# TN_Deck__Main_Board.net
KiCad netlist of a schematic drawn in EAGLE
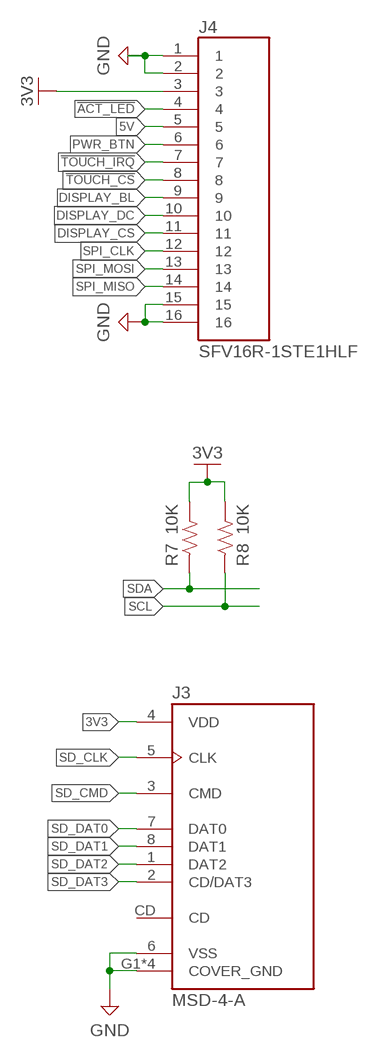
[diagram p0: schematic, sheet 1, part 1 of 2]
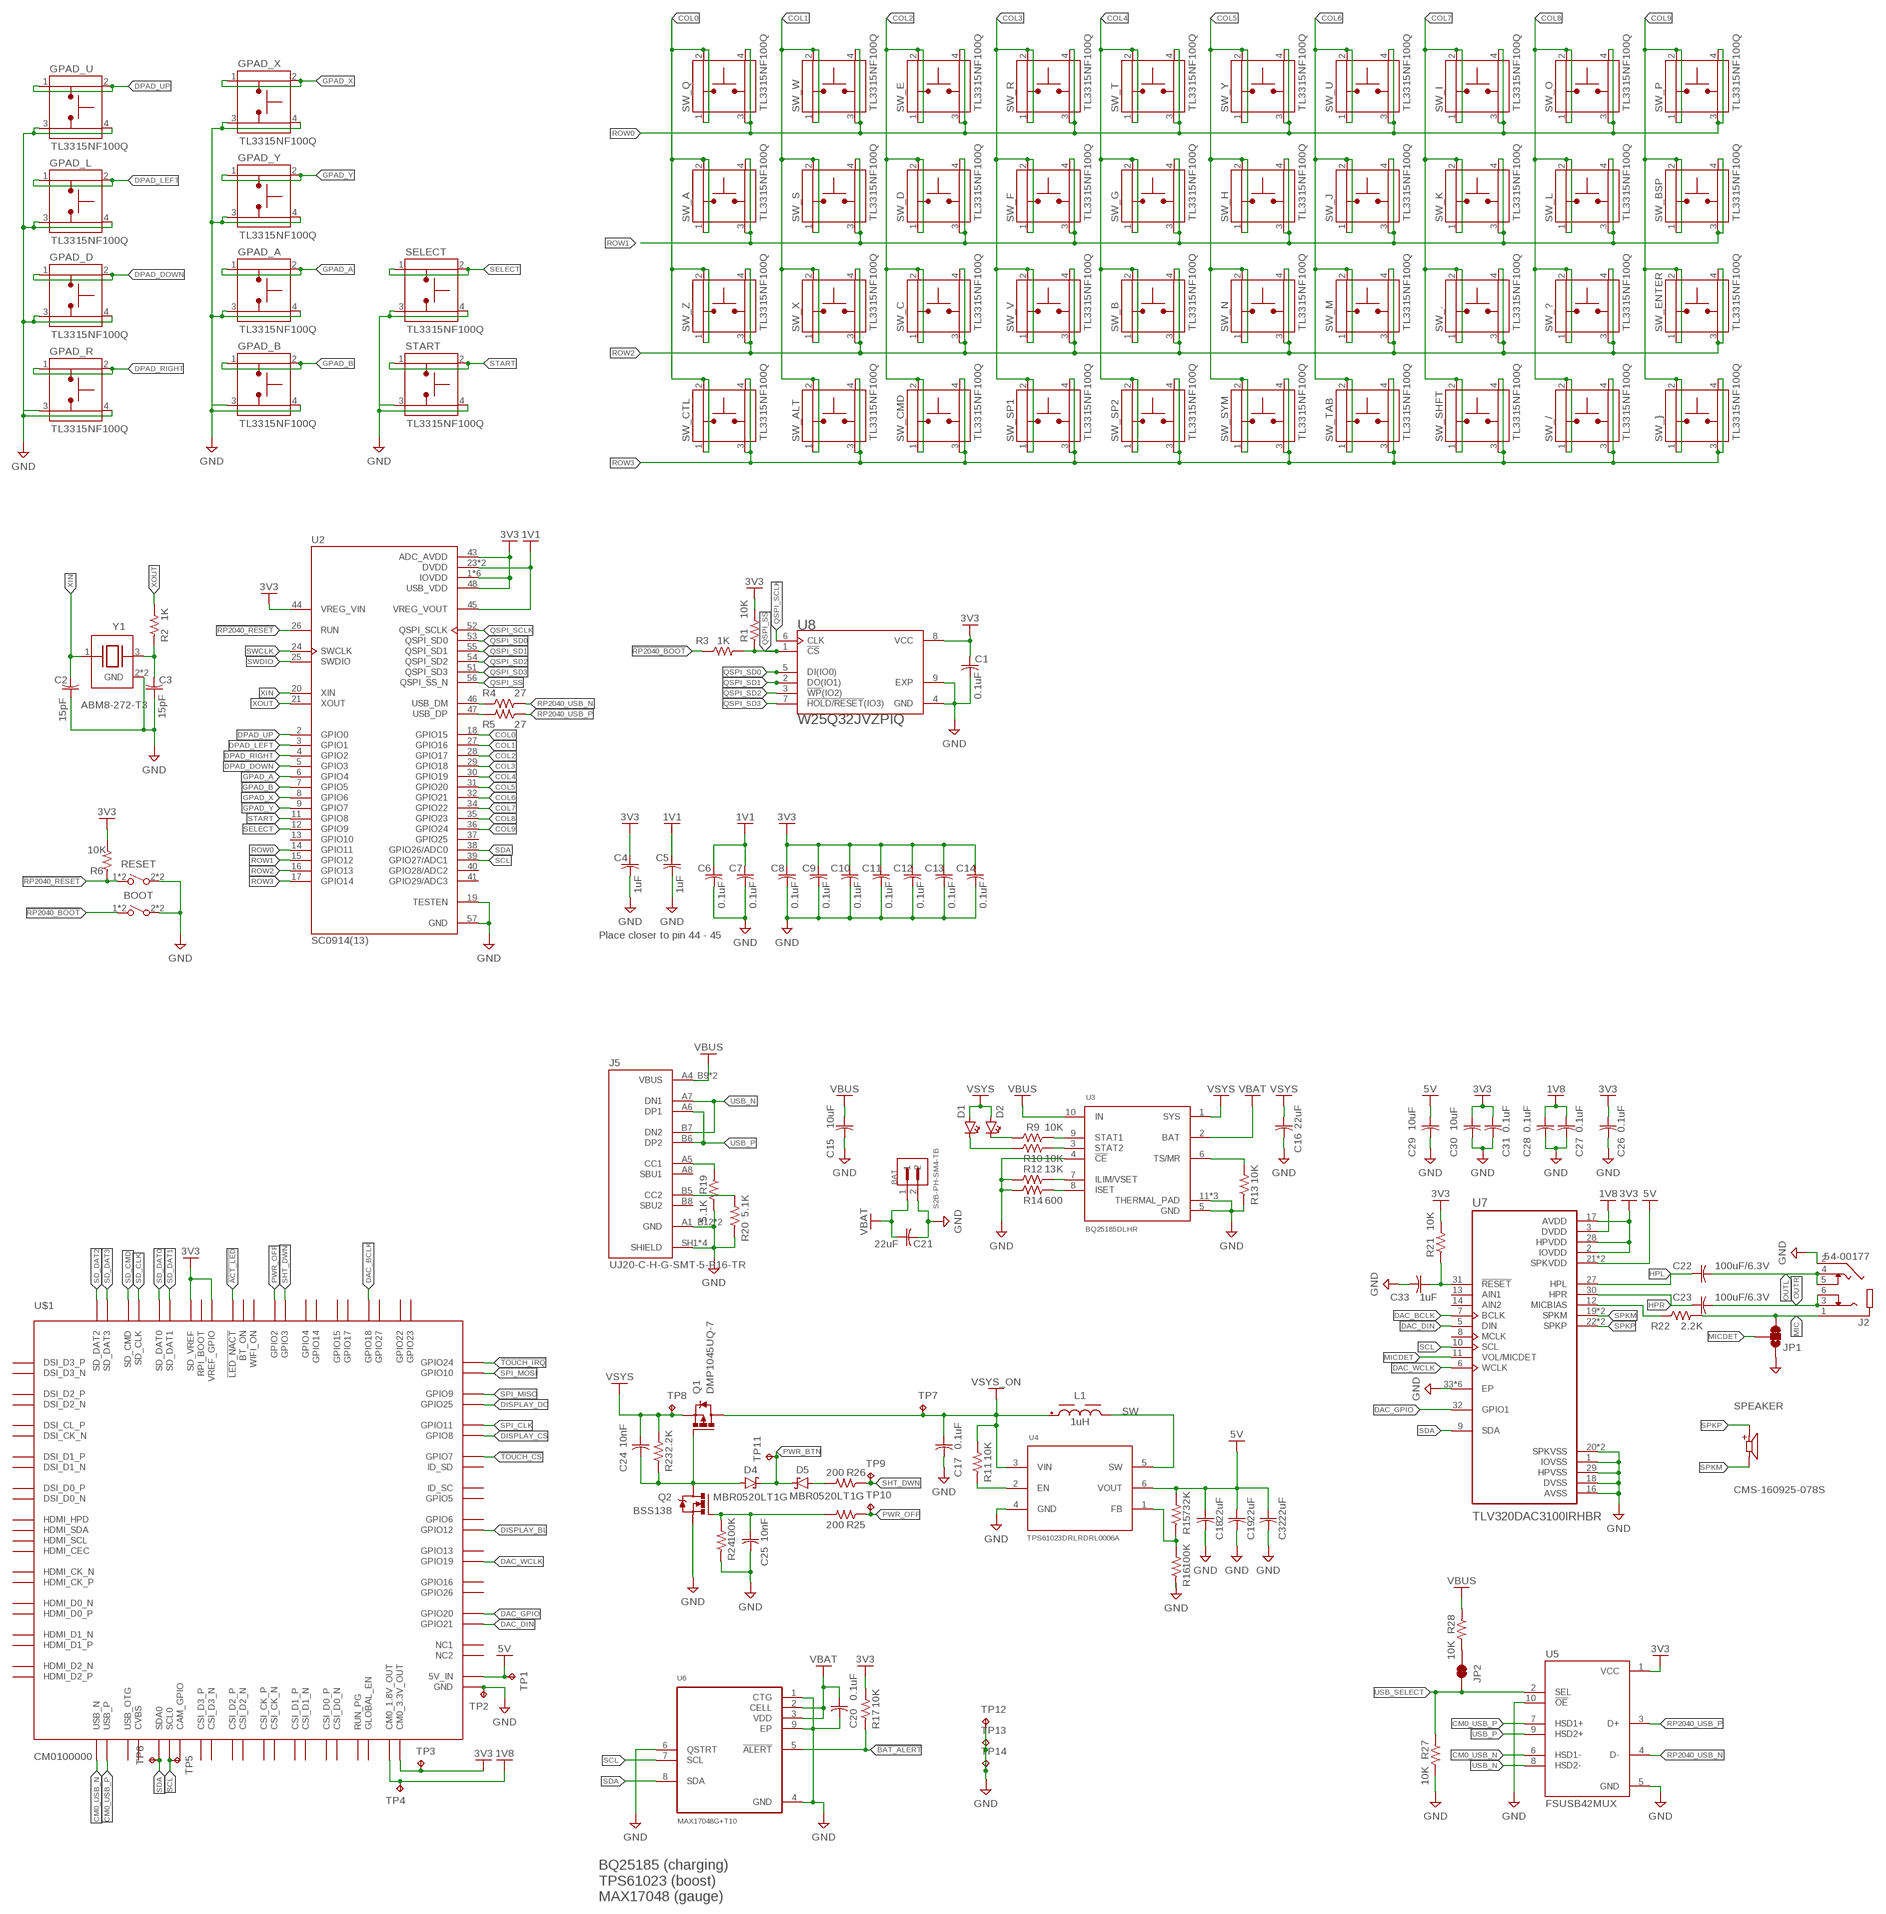
[diagram p1: schematic, sheet 1, part 2 of 2]

(export (version "E")
  (design (tool "Eeschema 10.0.6"))
  (components
    (comp (ref "BAT")
      (value "S2B-PH-SM4-TB")
      (footprint "eagle-import:JST_S2B-PH-SM4-TB")
      (fields
        (field (name "MANUFACTURER") "JST")
        (field (name "VENDOR") "Digikey")
        (field (name "VPN") "455-S2B-PH-SM4-TBCT-ND")
      )
      (libsource (lib "eagle-import") (part "S2B-PH-SM4-TB"))
    )
    (comp (ref "BOOT")
      (value "SPST-NO_SWITCH_KMR2")
      (footprint "eagle-import:KMR2")
      (fields
        (field (name "MANUFACTURER") "C&K")
        (field (name "MPN") "KMR211G LFS")
        (field (name "VENDOR") "Digikey")
        (field (name "VPN") "401-1426-1-ND")
      )
      (libsource (lib "eagle-import") (part "SPST-NO_SWITCH_KMR2"))
    )
    (comp (ref "C1")
      (value "0.1uF")
      (footprint "eagle-import:CAPC1608X85")
      (fields (field (name "VENDOR") "Digikey") (field (name "VPN") "399-C0603C104K3RACTUCT-ND"))
      (libsource (lib "eagle-import") (part "C-USCHIP-0603(1608-METRIC)_"))
    )
    (comp (ref "C2")
      (value "15pF")
      (footprint "eagle-import:CAPC1608X85")
      (fields (field (name "VENDOR") "Digikey") (field (name "VPN") "732-7761-1-ND"))
      (libsource (lib "eagle-import") (part "C-USCHIP-0603(1608-METRIC)_"))
    )
    (comp (ref "C3")
      (value "15pF")
      (footprint "eagle-import:CAPC1608X85")
      (fields (field (name "VENDOR") "Digikey") (field (name "VPN") "732-7761-1-ND"))
      (libsource (lib "eagle-import") (part "C-USCHIP-0603(1608-METRIC)_"))
    )
    (comp (ref "C4")
      (value "1uF")
      (footprint "eagle-import:CAPC1608X85")
      (fields (field (name "VENDOR") "Digikey") (field (name "VPN") "399-C0603C105K4RACTUCT-ND"))
      (libsource (lib "eagle-import") (part "C-USCHIP-0603(1608-METRIC)_"))
    )
    (comp (ref "C5")
      (value "1uF")
      (footprint "eagle-import:CAPC1608X85")
      (fields (field (name "VENDOR") "Digikey") (field (name "VPN") "399-C0603C105K4RACTUCT-ND"))
      (libsource (lib "eagle-import") (part "C-USCHIP-0603(1608-METRIC)_"))
    )
    (comp (ref "C6")
      (value "0.1uF")
      (footprint "eagle-import:CAPC1608X85")
      (fields (field (name "VENDOR") "Digikey") (field (name "VPN") "399-C0603C104K3RACTUCT-ND"))
      (libsource (lib "eagle-import") (part "C-USCHIP-0603(1608-METRIC)_"))
    )
    (comp (ref "C7")
      (value "0.1uF")
      (footprint "eagle-import:CAPC1608X85")
      (fields (field (name "VENDOR") "Digikey") (field (name "VPN") "399-C0603C104K3RACTUCT-ND"))
      (libsource (lib "eagle-import") (part "C-USCHIP-0603(1608-METRIC)_"))
    )
    (comp (ref "C8")
      (value "0.1uF")
      (footprint "eagle-import:CAPC1608X85")
      (fields (field (name "VENDOR") "Digikey") (field (name "VPN") "399-C0603C104K3RACTUCT-ND"))
      (libsource (lib "eagle-import") (part "C-USCHIP-0603(1608-METRIC)_"))
    )
    (comp (ref "C9")
      (value "0.1uF")
      (footprint "eagle-import:CAPC1608X85")
      (fields (field (name "VENDOR") "Digikey") (field (name "VPN") "399-C0603C104K3RACTUCT-ND"))
      (libsource (lib "eagle-import") (part "C-USCHIP-0603(1608-METRIC)_"))
    )
    (comp (ref "C10")
      (value "0.1uF")
      (footprint "eagle-import:CAPC1608X85")
      (fields (field (name "VENDOR") "Digikey") (field (name "VPN") "399-C0603C104K3RACTUCT-ND"))
      (libsource (lib "eagle-import") (part "C-USCHIP-0603(1608-METRIC)_"))
    )
    (comp (ref "C11")
      (value "0.1uF")
      (footprint "eagle-import:CAPC1608X85")
      (fields (field (name "VENDOR") "Digikey") (field (name "VPN") "399-C0603C104K3RACTUCT-ND"))
      (libsource (lib "eagle-import") (part "C-USCHIP-0603(1608-METRIC)_"))
    )
    (comp (ref "C12")
      (value "0.1uF")
      (footprint "eagle-import:CAPC1608X85")
      (fields (field (name "VENDOR") "Digikey") (field (name "VPN") "399-C0603C104K3RACTUCT-ND"))
      (libsource (lib "eagle-import") (part "C-USCHIP-0603(1608-METRIC)_"))
    )
    (comp (ref "C13")
      (value "0.1uF")
      (footprint "eagle-import:CAPC1608X85")
      (fields (field (name "VENDOR") "Digikey") (field (name "VPN") "399-C0603C104K3RACTUCT-ND"))
      (libsource (lib "eagle-import") (part "C-USCHIP-0603(1608-METRIC)_"))
    )
    (comp (ref "C14")
      (value "0.1uF")
      (footprint "eagle-import:CAPC1608X85")
      (fields (field (name "VENDOR") "Digikey") (field (name "VPN") "399-C0603C104K3RACTUCT-ND"))
      (libsource (lib "eagle-import") (part "C-USCHIP-0603(1608-METRIC)_"))
    )
    (comp (ref "C15")
      (value "10uF")
      (footprint "eagle-import:CAPC2012X110")
      (fields (field (name "VENDOR") "Digikey") (field (name "VPN") "1292-0805X106K250CT-ND"))
      (libsource (lib "eagle-import") (part "C-USCHIP-0805(2012-METRIC)_"))
    )
    (comp (ref "C16")
      (value "22uF")
      (footprint "eagle-import:CAPC2012X110")
      (fields (field (name "VENDOR") "Digikey") (field (name "VPN") "4713-GMC21X5R226M16NTCT-ND"))
      (libsource (lib "eagle-import") (part "C-USCHIP-0805(2012-METRIC)_"))
    )
    (comp (ref "C17")
      (value "0.1uF")
      (footprint "eagle-import:CAPC1608X85")
      (fields (field (name "VENDOR") "Digikey") (field (name "VPN") "399-C0603C104K3RACTUCT-ND"))
      (libsource (lib "eagle-import") (part "C-USCHIP-0603(1608-METRIC)_"))
    )
    (comp (ref "C18")
      (value "22uF")
      (footprint "eagle-import:CAPC2012X110")
      (fields (field (name "VENDOR") "Digikey") (field (name "VPN") "4713-GMC21X5R226M16NTCT-ND"))
      (libsource (lib "eagle-import") (part "C-USCHIP-0805(2012-METRIC)_"))
    )
    (comp (ref "C19")
      (value "22uF")
      (footprint "eagle-import:CAPC2012X110")
      (fields (field (name "VENDOR") "Digikey") (field (name "VPN") "4713-GMC21X5R226M16NTCT-ND"))
      (libsource (lib "eagle-import") (part "C-USCHIP-0805(2012-METRIC)_"))
    )
    (comp (ref "C20")
      (value "0.1uF")
      (footprint "eagle-import:CAPC1608X85")
      (fields (field (name "VENDOR") "Digikey") (field (name "VPN") "399-C0603C104K3RACTUCT-ND"))
      (libsource (lib "eagle-import") (part "C-USCHIP-0603(1608-METRIC)_"))
    )
    (comp (ref "C21")
      (value "22uF")
      (footprint "eagle-import:CAPC2012X110")
      (fields (field (name "VENDOR") "Digikey") (field (name "VPN") "4713-GMC21X5R226M16NTCT-ND"))
      (libsource (lib "eagle-import") (part "C-USCHIP-0805(2012-METRIC)_"))
    )
    (comp (ref "C22")
      (value "100uF/6.3V")
      (footprint "eagle-import:CAPC3216X135")
      (fields (field (name "VENDOR") "Digikey") (field (name "VPN") "1276-CL31A107MQHNNWECT-ND"))
      (libsource (lib "eagle-import") (part "C-USCHIP-1206(3216-METRIC)_"))
    )
    (comp (ref "C23")
      (value "100uF/6.3V")
      (footprint "eagle-import:CAPC3216X135")
      (fields (field (name "VENDOR") "Digikey") (field (name "VPN") "1276-CL31A107MQHNNWECT-ND"))
      (libsource (lib "eagle-import") (part "C-USCHIP-1206(3216-METRIC)_"))
    )
    (comp (ref "C24")
      (value "10nF")
      (footprint "eagle-import:CAPC1608X85")
      (fields (field (name "VENDOR") "Digikey") (field (name "VPN") "399-C0603C103K4RACTUCT-ND"))
      (libsource (lib "eagle-import") (part "C-USCHIP-0603(1608-METRIC)_"))
    )
    (comp (ref "C25")
      (value "10nF")
      (footprint "eagle-import:CAPC1608X85")
      (fields (field (name "VENDOR") "Digikey") (field (name "VPN") "399-C0603C103K4RACTUCT-ND"))
      (libsource (lib "eagle-import") (part "C-USCHIP-0603(1608-METRIC)_"))
    )
    (comp (ref "C26")
      (value "0.1uF")
      (footprint "eagle-import:CAPC1608X85")
      (fields (field (name "VENDOR") "Digikey") (field (name "VPN") "399-C0603C104K3RACTUCT-ND"))
      (libsource (lib "eagle-import") (part "C-USCHIP-0603(1608-METRIC)_"))
    )
    (comp (ref "C27")
      (value "0.1uF")
      (footprint "eagle-import:CAPC1608X85")
      (fields (field (name "VENDOR") "Digikey") (field (name "VPN") "399-C0603C104K3RACTUCT-ND"))
      (libsource (lib "eagle-import") (part "C-USCHIP-0603(1608-METRIC)_"))
    )
    (comp (ref "C28")
      (value "0.1uF")
      (footprint "eagle-import:CAPC1608X85")
      (fields (field (name "VENDOR") "Digikey") (field (name "VPN") "399-C0603C104K3RACTUCT-ND"))
      (libsource (lib "eagle-import") (part "C-USCHIP-0603(1608-METRIC)_"))
    )
    (comp (ref "C29")
      (value "10uF")
      (footprint "eagle-import:CAPC2012X110")
      (fields (field (name "VENDOR") "Digikey") (field (name "VPN") "1292-0805X106K250CT-ND"))
      (libsource (lib "eagle-import") (part "C-USCHIP-0805(2012-METRIC)_"))
    )
    (comp (ref "C30")
      (value "10uF")
      (footprint "eagle-import:CAPC2012X110")
      (fields (field (name "VENDOR") "Digikey") (field (name "VPN") "1292-0805X106K250CT-ND"))
      (libsource (lib "eagle-import") (part "C-USCHIP-0805(2012-METRIC)_"))
    )
    (comp (ref "C31")
      (value "0.1uF")
      (footprint "eagle-import:CAPC1608X85")
      (fields (field (name "VENDOR") "Digikey") (field (name "VPN") "399-C0603C104K3RACTUCT-ND"))
      (libsource (lib "eagle-import") (part "C-USCHIP-0603(1608-METRIC)_"))
    )
    (comp (ref "C32")
      (value "22uF")
      (footprint "eagle-import:CAPC2012X110")
      (fields (field (name "VENDOR") "Digikey") (field (name "VPN") "4713-GMC21X5R226M16NTCT-ND"))
      (libsource (lib "eagle-import") (part "C-USCHIP-0805(2012-METRIC)_"))
    )
    (comp (ref "C33")
      (value "1uF")
      (footprint "eagle-import:CAPC1608X85")
      (fields (field (name "VENDOR") "Digikey") (field (name "VPN") "399-C0603C104K3RACTUCT-ND"))
      (libsource (lib "eagle-import") (part "C-USCHIP-0603(1608-METRIC)_"))
    )
    (comp (ref "D1")
      (value "CHIP-FLAT-G_0603-0.80MM")
      (footprint "eagle-import:LEDC1608X80N_FLAT-G")
      (fields (field (name "VENDOR") "Digikey") (field (name "VPN") "732-4980-1-ND"))
      (libsource (lib "eagle-import") (part "CHIP-FLAT-G_0603-0.80MM"))
    )
    (comp (ref "D2")
      (value "CHIP-FLAT-R_0603-0.80MM")
      (footprint "eagle-import:LEDC1608X80N_FLAT-R")
      (fields (field (name "VENDOR") "Digikey") (field (name "VPN") "732-4978-1-ND"))
      (libsource (lib "eagle-import") (part "CHIP-FLAT-R_0603-0.80MM"))
    )
    (comp (ref "D4")
      (value "MBR0520LT1G")
      (footprint "eagle-import:SODFL3718X115")
      (fields
        (field (name "MANUFACTURER") "ON Semiconductor")
        (field (name "VENDOR") "Digikey")
        (field (name "VPN") "MBR0520LT1GOSCT-ND")
      )
      (libsource (lib "eagle-import") (part "SCHOTTKY_DO-219MBR0520LT1G"))
    )
    (comp (ref "D5")
      (value "MBR0520LT1G")
      (footprint "eagle-import:SODFL3718X115")
      (fields
        (field (name "MANUFACTURER") "ON Semiconductor")
        (field (name "VENDOR") "Digikey")
        (field (name "VPN") "MBR0520LT1GOSCT-ND")
      )
      (libsource (lib "eagle-import") (part "SCHOTTKY_DO-219MBR0520LT1G"))
    )
    (comp (ref "GPAD_A")
      (value "TL3315NF100Q")
      (footprint "eagle-import:TL3315NF100Q")
      (fields
        (field (name "MANUFACTURER") "E-Switch")
        (field (name "DIGIKEY_PARTNO") "EG4620TR-ND")
        (field (name "VENDOR") "Digikey")
        (field (name "VPN") "EG4620CT-ND")
        (field (name "CREATED_BY") "PCBLayout.com")
      )
      (libsource (lib "eagle-import") (part "TL3315NF100Q"))
    )
    (comp (ref "GPAD_B")
      (value "TL3315NF100Q")
      (footprint "eagle-import:TL3315NF100Q")
      (fields
        (field (name "MANUFACTURER") "E-Switch")
        (field (name "DIGIKEY_PARTNO") "EG4620TR-ND")
        (field (name "VENDOR") "Digikey")
        (field (name "VPN") "EG4620CT-ND")
        (field (name "CREATED_BY") "PCBLayout.com")
      )
      (libsource (lib "eagle-import") (part "TL3315NF100Q"))
    )
    (comp (ref "GPAD_D")
      (value "TL3315NF100Q")
      (footprint "eagle-import:TL3315NF100Q")
      (fields
        (field (name "MANUFACTURER") "E-Switch")
        (field (name "DIGIKEY_PARTNO") "EG4620TR-ND")
        (field (name "VENDOR") "Digikey")
        (field (name "VPN") "EG4620CT-ND")
        (field (name "CREATED_BY") "PCBLayout.com")
      )
      (libsource (lib "eagle-import") (part "TL3315NF100Q"))
    )
    (comp (ref "GPAD_L")
      (value "TL3315NF100Q")
      (footprint "eagle-import:TL3315NF100Q")
      (fields
        (field (name "MANUFACTURER") "E-Switch")
        (field (name "DIGIKEY_PARTNO") "EG4620TR-ND")
        (field (name "VENDOR") "Digikey")
        (field (name "VPN") "EG4620CT-ND")
        (field (name "CREATED_BY") "PCBLayout.com")
      )
      (libsource (lib "eagle-import") (part "TL3315NF100Q"))
    )
    (comp (ref "GPAD_R")
      (value "TL3315NF100Q")
      (footprint "eagle-import:TL3315NF100Q")
      (fields
        (field (name "MANUFACTURER") "E-Switch")
        (field (name "DIGIKEY_PARTNO") "EG4620TR-ND")
        (field (name "VENDOR") "Digikey")
        (field (name "VPN") "EG4620CT-ND")
        (field (name "CREATED_BY") "PCBLayout.com")
      )
      (libsource (lib "eagle-import") (part "TL3315NF100Q"))
    )
    (comp (ref "GPAD_U")
      (value "TL3315NF100Q")
      (footprint "eagle-import:TL3315NF100Q")
      (fields
        (field (name "MANUFACTURER") "E-Switch")
        (field (name "DIGIKEY_PARTNO") "EG4620TR-ND")
        (field (name "VENDOR") "Digikey")
        (field (name "VPN") "EG4620CT-ND")
        (field (name "CREATED_BY") "PCBLayout.com")
      )
      (libsource (lib "eagle-import") (part "TL3315NF100Q"))
    )
    (comp (ref "GPAD_X")
      (value "TL3315NF100Q")
      (footprint "eagle-import:TL3315NF100Q")
      (fields
        (field (name "MANUFACTURER") "E-Switch")
        (field (name "DIGIKEY_PARTNO") "EG4620TR-ND")
        (field (name "VENDOR") "Digikey")
        (field (name "VPN") "EG4620CT-ND")
        (field (name "CREATED_BY") "PCBLayout.com")
      )
      (libsource (lib "eagle-import") (part "TL3315NF100Q"))
    )
    (comp (ref "GPAD_Y")
      (value "TL3315NF100Q")
      (footprint "eagle-import:TL3315NF100Q")
      (fields
        (field (name "MANUFACTURER") "E-Switch")
        (field (name "DIGIKEY_PARTNO") "EG4620TR-ND")
        (field (name "VENDOR") "Digikey")
        (field (name "VPN") "EG4620CT-ND")
        (field (name "CREATED_BY") "PCBLayout.com")
      )
      (libsource (lib "eagle-import") (part "TL3315NF100Q"))
    )
    (comp (ref "J2")
      (value "54-00177")
      (footprint "eagle-import:TENSILITY_54-00177")
      (fields
        (field (name "MANUFACTURER") "TENSILITY")
        (field (name "VENDOR") "Digikey")
        (field (name "VPN") "839-54-00177CT-ND")
      )
      (libsource (lib "eagle-import") (part "54-00177"))
    )
    (comp (ref "J3")
      (value "MSD-4-A")
      (footprint "eagle-import:CUI_MSD-4-A")
      (fields
        (field (name "MANUFACTURER") "CUI Devices")
        (field (name "VENDOR") "Digikey")
        (field (name "VPN") "2223-MSD-4-ACT-ND")
      )
      (libsource (lib "eagle-import") (part "MSD-4-A"))
    )
    (comp (ref "J4")
      (value "SFV16R-1STE1HLF")
      (footprint "eagle-import:AMPHENOL_SFV16R-1STE1HLF")
      (fields
        (field (name "MANUFACTURER") "Amphenol")
        (field (name "VENDOR") "Digikey")
        (field (name "VPN") "609-4313-1-ND")
      )
      (libsource (lib "eagle-import") (part "SFV16R-1STE1HLF"))
    )
    (comp (ref "J5")
      (value "UJ20-C-H-G-SMT-5-P16-TR")
      (footprint "eagle-import:SAMESKY_UJ20-C-H-G-SMT-5-P16-TR")
      (fields
        (field (name "MANUFACTURER") "Same Sky")
        (field (name "VENDOR") "Digikey")
        (field (name "VPN") "2223-UJ20-C-H-G-SMT-5-P16-TRCT-ND")
        (field (name "CREATOR") "AMINA")
        (field (name "VERIFIER") "Your name, use the same always")
      )
      (libsource (lib "eagle-import") (part "UJ20-C-H-G-SMT-5-P16-TR"))
    )
    (comp (ref "JP1")
      (value "JUMPER-SMT_3_1-NC_TRACE_SILK")
      (footprint "eagle-import:SMT-JUMPER_3_1-NC_TRACE_SILK")
      (libsource (lib "eagle-import") (part "JUMPER-SMT_3_1-NC_TRACE_SILK"))
    )
    (comp (ref "JP2")
      (value "JUMPER-SMT_2_NC_TRACE_NO-SILK")
      (footprint "eagle-import:SMT-JUMPER_2_NC_TRACE_NO-SILK")
      (libsource (lib "eagle-import") (part "JUMPER-SMT_2_NC_TRACE_NO-SILK"))
    )
    (comp (ref "L1")
      (value "1uH")
      (footprint "eagle-import:WE-XHMI_4020")
      (fields (field (name "VENDOR") "Digikey") (field (name "VPN") "732-11310-1-ND"))
      (libsource (lib "eagle-import") (part "WE-XHMI_4020_74439323010"))
    )
    (comp (ref "Q1")
      (value "DMP1045UQ-7")
      (footprint "eagle-import:SOT23")
      (fields (field (name "VENDOR") "Digikey") (field (name "VPN") "31-DMP1045UQ-7CT-ND"))
      (libsource (lib "eagle-import") (part "PMOSFETSOT23-GSD_"))
    )
    (comp (ref "Q2")
      (value "BSS138")
      (footprint "eagle-import:SOT23")
      (fields (field (name "VENDOR") "Digikey") (field (name "VPN") "BSS138CT-ND"))
      (libsource (lib "eagle-import") (part "NMOSFETSOT23-GSD_"))
    )
    (comp (ref "R1")
      (value "10K")
      (footprint "eagle-import:RESC1608X60")
      (fields (field (name "VENDOR") "Digikey") (field (name "VPN") "541-10.0KHCT-ND"))
      (libsource (lib "eagle-import") (part "R-USCHIP-0603(1608-METRIC)_"))
    )
    (comp (ref "R2")
      (value "1K")
      (footprint "eagle-import:RESC1608X60")
      (fields (field (name "VENDOR") "Digikey") (field (name "VPN") "541-1.00KHCT-ND"))
      (libsource (lib "eagle-import") (part "R-USCHIP-0603(1608-METRIC)_"))
    )
    (comp (ref "R3")
      (value "1K")
      (footprint "eagle-import:RESC1608X60")
      (fields (field (name "VENDOR") "Digikey") (field (name "VPN") "541-1.00KHCT-ND"))
      (libsource (lib "eagle-import") (part "R-USCHIP-0603(1608-METRIC)_"))
    )
    (comp (ref "R4")
      (value "27")
      (footprint "eagle-import:RESC1608X60")
      (fields (field (name "VENDOR") "Digikey") (field (name "VPN") "541-27.0HCT-ND"))
      (libsource (lib "eagle-import") (part "R-USCHIP-0603(1608-METRIC)_"))
    )
    (comp (ref "R5")
      (value "27")
      (footprint "eagle-import:RESC1608X60")
      (fields (field (name "VENDOR") "Digikey") (field (name "VPN") "541-27.0HCT-ND"))
      (libsource (lib "eagle-import") (part "R-USCHIP-0603(1608-METRIC)_"))
    )
    (comp (ref "R6")
      (value "10K")
      (footprint "eagle-import:RESC1608X60")
      (fields (field (name "VENDOR") "Digikey") (field (name "VPN") "541-10.0KHCT-ND"))
      (libsource (lib "eagle-import") (part "R-USCHIP-0603(1608-METRIC)_"))
    )
    (comp (ref "R7")
      (value "10K")
      (footprint "eagle-import:RESC1608X60")
      (fields (field (name "VENDOR") "Digikey") (field (name "VPN") "541-10.0KHCT-ND"))
      (libsource (lib "eagle-import") (part "R-USCHIP-0603(1608-METRIC)_"))
    )
    (comp (ref "R8")
      (value "10K")
      (footprint "eagle-import:RESC1608X60")
      (fields (field (name "VENDOR") "Digikey") (field (name "VPN") "541-10.0KHCT-ND"))
      (libsource (lib "eagle-import") (part "R-USCHIP-0603(1608-METRIC)_"))
    )
    (comp (ref "R9")
      (value "10K")
      (footprint "eagle-import:RESC1608X60")
      (fields (field (name "VENDOR") "Digikey") (field (name "VPN") "541-10.0KHCT-ND"))
      (libsource (lib "eagle-import") (part "R-USCHIP-0603(1608-METRIC)_"))
    )
    (comp (ref "R10")
      (value "10K")
      (footprint "eagle-import:RESC1608X60")
      (fields (field (name "VENDOR") "Digikey") (field (name "VPN") "541-10.0KHCT-ND"))
      (libsource (lib "eagle-import") (part "R-USCHIP-0603(1608-METRIC)_"))
    )
    (comp (ref "R11")
      (value "10K")
      (footprint "eagle-import:RESC1608X60")
      (fields (field (name "VENDOR") "Digikey") (field (name "VPN") "541-10.0KHCT-ND"))
      (libsource (lib "eagle-import") (part "R-USCHIP-0603(1608-METRIC)_"))
    )
    (comp (ref "R12")
      (value "13K")
      (footprint "eagle-import:RESC1608X60")
      (fields (field (name "VENDOR") "Digikey") (field (name "VPN") "541-13.0KHCT-ND"))
      (libsource (lib "eagle-import") (part "R-USCHIP-0603(1608-METRIC)_"))
    )
    (comp (ref "R13")
      (value "10K")
      (footprint "eagle-import:RESC1608X60")
      (fields (field (name "VENDOR") "Digikey") (field (name "VPN") "541-10.0KHCT-ND"))
      (libsource (lib "eagle-import") (part "R-USCHIP-0603(1608-METRIC)_"))
    )
    (comp (ref "R14")
      (value "600")
      (footprint "eagle-import:RESC1608X60")
      (fields (field (name "VENDOR") "Digikey") (field (name "VPN") "541-604HCT-ND"))
      (libsource (lib "eagle-import") (part "R-USCHIP-0603(1608-METRIC)_"))
    )
    (comp (ref "R15")
      (value "732K")
      (footprint "eagle-import:RESC1608X60")
      (fields (field (name "VENDOR") "Digikey") (field (name "VPN") "541-732KHCT-ND"))
      (libsource (lib "eagle-import") (part "R-USCHIP-0603(1608-METRIC)_"))
    )
    (comp (ref "R16")
      (value "100K")
      (footprint "eagle-import:RESC1608X60")
      (fields (field (name "VENDOR") "Digikey") (field (name "VPN") "541-100KHCT-ND"))
      (libsource (lib "eagle-import") (part "R-USCHIP-0603(1608-METRIC)_"))
    )
    (comp (ref "R17")
      (value "10K")
      (footprint "eagle-import:RESC1608X60")
      (fields (field (name "VENDOR") "Digikey") (field (name "VPN") "541-10.0KHCT-ND"))
      (libsource (lib "eagle-import") (part "R-USCHIP-0603(1608-METRIC)_"))
    )
    (comp (ref "R19")
      (value "5.1K")
      (footprint "eagle-import:RESC1608X60")
      (fields (field (name "VENDOR") "Digikey") (field (name "VPN") "541-5.10KHCT-ND"))
      (libsource (lib "eagle-import") (part "R-USCHIP-0603(1608-METRIC)_"))
    )
    (comp (ref "R20")
      (value "5.1K")
      (footprint "eagle-import:RESC1608X60")
      (fields (field (name "VENDOR") "Digikey") (field (name "VPN") "541-5.10KHCT-ND"))
      (libsource (lib "eagle-import") (part "R-USCHIP-0603(1608-METRIC)_"))
    )
    (comp (ref "R21")
      (value "10K")
      (footprint "eagle-import:RESC1608X60")
      (fields (field (name "VENDOR") "Digikey") (field (name "VPN") "541-10.0KHCT-ND"))
      (libsource (lib "eagle-import") (part "R-USCHIP-0603(1608-METRIC)_"))
    )
    (comp (ref "R22")
      (value "2.2K")
      (footprint "eagle-import:RESC1608X60")
      (fields (field (name "VENDOR") "Digikey") (field (name "VPN") "541-2.20KHCT-ND"))
      (libsource (lib "eagle-import") (part "R-USCHIP-0603(1608-METRIC)_"))
    )
    (comp (ref "R23")
      (value "2.2K")
      (footprint "eagle-import:RESC1608X60")
      (fields (field (name "VENDOR") "Digikey") (field (name "VPN") "541-10.0KHCT-ND"))
      (libsource (lib "eagle-import") (part "R-USCHIP-0603(1608-METRIC)_"))
    )
    (comp (ref "R24")
      (value "100K")
      (footprint "eagle-import:RESC1608X60")
      (fields (field (name "VENDOR") "Digikey") (field (name "VPN") "541-100KHCT-ND"))
      (libsource (lib "eagle-import") (part "R-USCHIP-0603(1608-METRIC)_"))
    )
    (comp (ref "R25")
      (value "200")
      (footprint "eagle-import:RESC1608X60")
      (fields (field (name "VENDOR") "Digikey") (field (name "VPN") "541-200HCT-ND"))
      (libsource (lib "eagle-import") (part "R-USCHIP-0603(1608-METRIC)_"))
    )
    (comp (ref "R26")
      (value "200")
      (footprint "eagle-import:RESC1608X60")
      (fields (field (name "VENDOR") "Digikey") (field (name "VPN") "541-200HCT-ND"))
      (libsource (lib "eagle-import") (part "R-USCHIP-0603(1608-METRIC)_"))
    )
    (comp (ref "R27")
      (value "10K")
      (footprint "eagle-import:RESC1608X60")
      (fields (field (name "VENDOR") "Digikey") (field (name "VPN") "541-10.0KHCT-ND"))
      (libsource (lib "eagle-import") (part "R-USCHIP-0603(1608-METRIC)_"))
    )
    (comp (ref "R28")
      (value "10K")
      (footprint "eagle-import:RESC1608X60")
      (fields (field (name "VENDOR") "Digikey") (field (name "VPN") "541-10.0KHCT-ND"))
      (libsource (lib "eagle-import") (part "R-USCHIP-0603(1608-METRIC)_"))
    )
    (comp (ref "RESET")
      (value "SPST-NO_SWITCH_KMR2")
      (footprint "eagle-import:KMR2")
      (fields
        (field (name "MANUFACTURER") "C&K")
        (field (name "MPN") "KMR211G LFS")
        (field (name "VENDOR") "Digikey")
        (field (name "VPN") "401-1426-1-ND")
      )
      (libsource (lib "eagle-import") (part "SPST-NO_SWITCH_KMR2"))
    )
    (comp (ref "SELECT")
      (value "TL3315NF100Q")
      (footprint "eagle-import:TL3315NF100Q")
      (fields
        (field (name "MANUFACTURER") "E-Switch")
        (field (name "DIGIKEY_PARTNO") "EG4620TR-ND")
        (field (name "VENDOR") "Digikey")
        (field (name "VPN") "EG4620CT-ND")
        (field (name "CREATED_BY") "PCBLayout.com")
      )
      (libsource (lib "eagle-import") (part "TL3315NF100Q"))
    )
    (comp (ref "SPEAKER")
      (value "CMS-160925-078S")
      (footprint "eagle-import:SPKR_CMS-160925-078S")
      (fields
        (field (name "MANUFACTURER") "CUI INC")
        (field (name "VENDOR") "Digikey")
        (field (name "VPN") "102-4619-ND")
      )
      (libsource (lib "eagle-import") (part "CMS-160925-078S"))
    )
    (comp (ref "START")
      (value "TL3315NF100Q")
      (footprint "eagle-import:TL3315NF100Q")
      (fields
        (field (name "MANUFACTURER") "E-Switch")
        (field (name "DIGIKEY_PARTNO") "EG4620TR-ND")
        (field (name "VENDOR") "Digikey")
        (field (name "VPN") "EG4620CT-ND")
        (field (name "CREATED_BY") "PCBLayout.com")
      )
      (libsource (lib "eagle-import") (part "TL3315NF100Q"))
    )
    (comp (ref "SW_.")
      (value "TL3315NF100Q")
      (footprint "eagle-import:TL3315NF100Q")
      (fields
        (field (name "MANUFACTURER") "E-Switch")
        (field (name "DIGIKEY_PARTNO") "EG4620TR-ND")
        (field (name "VENDOR") "Digikey")
        (field (name "VPN") "EG4620CT-ND")
        (field (name "CREATED_BY") "PCBLayout.com")
      )
      (libsource (lib "eagle-import") (part "TL3315NF100Q"))
    )
    (comp (ref "SW_/")
      (value "TL3315NF100Q")
      (footprint "eagle-import:TL3315NF100Q")
      (fields
        (field (name "MANUFACTURER") "E-Switch")
        (field (name "DIGIKEY_PARTNO") "EG4620TR-ND")
        (field (name "VENDOR") "Digikey")
        (field (name "VPN") "EG4620CT-ND")
        (field (name "CREATED_BY") "PCBLayout.com")
      )
      (libsource (lib "eagle-import") (part "TL3315NF100Q"))
    )
    (comp (ref "SW_?")
      (value "TL3315NF100Q")
      (footprint "eagle-import:TL3315NF100Q")
      (fields
        (field (name "MANUFACTURER") "E-Switch")
        (field (name "DIGIKEY_PARTNO") "EG4620TR-ND")
        (field (name "VENDOR") "Digikey")
        (field (name "VPN") "EG4620CT-ND")
        (field (name "CREATED_BY") "PCBLayout.com")
      )
      (libsource (lib "eagle-import") (part "TL3315NF100Q"))
    )
    (comp (ref "SW_A")
      (value "TL3315NF100Q")
      (footprint "eagle-import:TL3315NF100Q")
      (fields
        (field (name "MANUFACTURER") "E-Switch")
        (field (name "DIGIKEY_PARTNO") "EG4620TR-ND")
        (field (name "VENDOR") "Digikey")
        (field (name "VPN") "EG4620CT-ND")
        (field (name "CREATED_BY") "PCBLayout.com")
      )
      (libsource (lib "eagle-import") (part "TL3315NF100Q"))
    )
    (comp (ref "SW_ALT")
      (value "TL3315NF100Q")
      (footprint "eagle-import:TL3315NF100Q")
      (fields
        (field (name "MANUFACTURER") "E-Switch")
        (field (name "DIGIKEY_PARTNO") "EG4620TR-ND")
        (field (name "VENDOR") "Digikey")
        (field (name "VPN") "EG4620CT-ND")
        (field (name "CREATED_BY") "PCBLayout.com")
      )
      (libsource (lib "eagle-import") (part "TL3315NF100Q"))
    )
    (comp (ref "SW_B")
      (value "TL3315NF100Q")
      (footprint "eagle-import:TL3315NF100Q")
      (fields
        (field (name "MANUFACTURER") "E-Switch")
        (field (name "DIGIKEY_PARTNO") "EG4620TR-ND")
        (field (name "VENDOR") "Digikey")
        (field (name "VPN") "EG4620CT-ND")
        (field (name "CREATED_BY") "PCBLayout.com")
      )
      (libsource (lib "eagle-import") (part "TL3315NF100Q"))
    )
    (comp (ref "SW_BSP")
      (value "TL3315NF100Q")
      (footprint "eagle-import:TL3315NF100Q")
      (fields
        (field (name "MANUFACTURER") "E-Switch")
        (field (name "DIGIKEY_PARTNO") "EG4620TR-ND")
        (field (name "VENDOR") "Digikey")
        (field (name "VPN") "EG4620CT-ND")
        (field (name "CREATED_BY") "PCBLayout.com")
      )
      (libsource (lib "eagle-import") (part "TL3315NF100Q"))
    )
    (comp (ref "SW_C")
      (value "TL3315NF100Q")
      (footprint "eagle-import:TL3315NF100Q")
      (fields
        (field (name "MANUFACTURER") "E-Switch")
        (field (name "DIGIKEY_PARTNO") "EG4620TR-ND")
        (field (name "VENDOR") "Digikey")
        (field (name "VPN") "EG4620CT-ND")
        (field (name "CREATED_BY") "PCBLayout.com")
      )
      (libsource (lib "eagle-import") (part "TL3315NF100Q"))
    )
    (comp (ref "SW_CMD")
      (value "TL3315NF100Q")
      (footprint "eagle-import:TL3315NF100Q")
      (fields
        (field (name "MANUFACTURER") "E-Switch")
        (field (name "DIGIKEY_PARTNO") "EG4620TR-ND")
        (field (name "VENDOR") "Digikey")
        (field (name "VPN") "EG4620CT-ND")
        (field (name "CREATED_BY") "PCBLayout.com")
      )
      (libsource (lib "eagle-import") (part "TL3315NF100Q"))
    )
    (comp (ref "SW_CTL")
      (value "TL3315NF100Q")
      (footprint "eagle-import:TL3315NF100Q")
      (fields
        (field (name "MANUFACTURER") "E-Switch")
        (field (name "DIGIKEY_PARTNO") "EG4620TR-ND")
        (field (name "VENDOR") "Digikey")
        (field (name "VPN") "EG4620CT-ND")
        (field (name "CREATED_BY") "PCBLayout.com")
      )
      (libsource (lib "eagle-import") (part "TL3315NF100Q"))
    )
    (comp (ref "SW_D")
      (value "TL3315NF100Q")
      (footprint "eagle-import:TL3315NF100Q")
      (fields
        (field (name "MANUFACTURER") "E-Switch")
        (field (name "DIGIKEY_PARTNO") "EG4620TR-ND")
        (field (name "VENDOR") "Digikey")
        (field (name "VPN") "EG4620CT-ND")
        (field (name "CREATED_BY") "PCBLayout.com")
      )
      (libsource (lib "eagle-import") (part "TL3315NF100Q"))
    )
    (comp (ref "SW_E")
      (value "TL3315NF100Q")
      (footprint "eagle-import:TL3315NF100Q")
      (fields
        (field (name "MANUFACTURER") "E-Switch")
        (field (name "DIGIKEY_PARTNO") "EG4620TR-ND")
        (field (name "VENDOR") "Digikey")
        (field (name "VPN") "EG4620CT-ND")
        (field (name "CREATED_BY") "PCBLayout.com")
      )
      (libsource (lib "eagle-import") (part "TL3315NF100Q"))
    )
    (comp (ref "SW_ENTER")
      (value "TL3315NF100Q")
      (footprint "eagle-import:TL3315NF100Q")
      (fields
        (field (name "MANUFACTURER") "E-Switch")
        (field (name "DIGIKEY_PARTNO") "EG4620TR-ND")
        (field (name "VENDOR") "Digikey")
        (field (name "VPN") "EG4620CT-ND")
        (field (name "CREATED_BY") "PCBLayout.com")
      )
      (libsource (lib "eagle-import") (part "TL3315NF100Q"))
    )
    (comp (ref "SW_F")
      (value "TL3315NF100Q")
      (footprint "eagle-import:TL3315NF100Q")
      (fields
        (field (name "MANUFACTURER") "E-Switch")
        (field (name "DIGIKEY_PARTNO") "EG4620TR-ND")
        (field (name "VENDOR") "Digikey")
        (field (name "VPN") "EG4620CT-ND")
        (field (name "CREATED_BY") "PCBLayout.com")
      )
      (libsource (lib "eagle-import") (part "TL3315NF100Q"))
    )
    (comp (ref "SW_G")
      (value "TL3315NF100Q")
      (footprint "eagle-import:TL3315NF100Q")
      (fields
        (field (name "MANUFACTURER") "E-Switch")
        (field (name "DIGIKEY_PARTNO") "EG4620TR-ND")
        (field (name "VENDOR") "Digikey")
        (field (name "VPN") "EG4620CT-ND")
        (field (name "CREATED_BY") "PCBLayout.com")
      )
      (libsource (lib "eagle-import") (part "TL3315NF100Q"))
    )
    (comp (ref "SW_H")
      (value "TL3315NF100Q")
      (footprint "eagle-import:TL3315NF100Q")
      (fields
        (field (name "MANUFACTURER") "E-Switch")
        (field (name "DIGIKEY_PARTNO") "EG4620TR-ND")
        (field (name "VENDOR") "Digikey")
        (field (name "VPN") "EG4620CT-ND")
        (field (name "CREATED_BY") "PCBLayout.com")
      )
      (libsource (lib "eagle-import") (part "TL3315NF100Q"))
    )
    (comp (ref "SW_I")
      (value "TL3315NF100Q")
      (footprint "eagle-import:TL3315NF100Q")
      (fields
        (field (name "MANUFACTURER") "E-Switch")
        (field (name "DIGIKEY_PARTNO") "EG4620TR-ND")
        (field (name "VENDOR") "Digikey")
        (field (name "VPN") "EG4620CT-ND")
        (field (name "CREATED_BY") "PCBLayout.com")
      )
      (libsource (lib "eagle-import") (part "TL3315NF100Q"))
    )
    (comp (ref "SW_J")
      (value "TL3315NF100Q")
      (footprint "eagle-import:TL3315NF100Q")
      (fields
        (field (name "MANUFACTURER") "E-Switch")
        (field (name "DIGIKEY_PARTNO") "EG4620TR-ND")
        (field (name "VENDOR") "Digikey")
        (field (name "VPN") "EG4620CT-ND")
        (field (name "CREATED_BY") "PCBLayout.com")
      )
      (libsource (lib "eagle-import") (part "TL3315NF100Q"))
    )
    (comp (ref "SW_K")
      (value "TL3315NF100Q")
      (footprint "eagle-import:TL3315NF100Q")
      (fields
        (field (name "MANUFACTURER") "E-Switch")
        (field (name "DIGIKEY_PARTNO") "EG4620TR-ND")
        (field (name "VENDOR") "Digikey")
        (field (name "VPN") "EG4620CT-ND")
        (field (name "CREATED_BY") "PCBLayout.com")
      )
      (libsource (lib "eagle-import") (part "TL3315NF100Q"))
    )
    (comp (ref "SW_L")
      (value "TL3315NF100Q")
      (footprint "eagle-import:TL3315NF100Q")
      (fields
        (field (name "MANUFACTURER") "E-Switch")
        (field (name "DIGIKEY_PARTNO") "EG4620TR-ND")
        (field (name "VENDOR") "Digikey")
        (field (name "VPN") "EG4620CT-ND")
        (field (name "CREATED_BY") "PCBLayout.com")
      )
      (libsource (lib "eagle-import") (part "TL3315NF100Q"))
    )
    (comp (ref "SW_M")
      (value "TL3315NF100Q")
      (footprint "eagle-import:TL3315NF100Q")
      (fields
        (field (name "MANUFACTURER") "E-Switch")
        (field (name "DIGIKEY_PARTNO") "EG4620TR-ND")
        (field (name "VENDOR") "Digikey")
        (field (name "VPN") "EG4620CT-ND")
        (field (name "CREATED_BY") "PCBLayout.com")
      )
      (libsource (lib "eagle-import") (part "TL3315NF100Q"))
    )
    (comp (ref "SW_N")
      (value "TL3315NF100Q")
      (footprint "eagle-import:TL3315NF100Q")
      (fields
        (field (name "MANUFACTURER") "E-Switch")
        (field (name "DIGIKEY_PARTNO") "EG4620TR-ND")
        (field (name "VENDOR") "Digikey")
        (field (name "VPN") "EG4620CT-ND")
        (field (name "CREATED_BY") "PCBLayout.com")
      )
      (libsource (lib "eagle-import") (part "TL3315NF100Q"))
    )
    (comp (ref "SW_O")
      (value "TL3315NF100Q")
      (footprint "eagle-import:TL3315NF100Q")
      (fields
        (field (name "MANUFACTURER") "E-Switch")
        (field (name "DIGIKEY_PARTNO") "EG4620TR-ND")
        (field (name "VENDOR") "Digikey")
        (field (name "VPN") "EG4620CT-ND")
        (field (name "CREATED_BY") "PCBLayout.com")
      )
      (libsource (lib "eagle-import") (part "TL3315NF100Q"))
    )
    (comp (ref "SW_P")
      (value "TL3315NF100Q")
      (footprint "eagle-import:TL3315NF100Q")
      (fields
        (field (name "MANUFACTURER") "E-Switch")
        (field (name "DIGIKEY_PARTNO") "EG4620TR-ND")
        (field (name "VENDOR") "Digikey")
        (field (name "VPN") "EG4620CT-ND")
        (field (name "CREATED_BY") "PCBLayout.com")
      )
      (libsource (lib "eagle-import") (part "TL3315NF100Q"))
    )
    (comp (ref "SW_Q")
      (value "TL3315NF100Q")
      (footprint "eagle-import:TL3315NF100Q")
      (fields
        (field (name "MANUFACTURER") "E-Switch")
        (field (name "DIGIKEY_PARTNO") "EG4620TR-ND")
        (field (name "VENDOR") "Digikey")
        (field (name "VPN") "EG4620CT-ND")
        (field (name "CREATED_BY") "PCBLayout.com")
      )
      (libsource (lib "eagle-import") (part "TL3315NF100Q"))
    )
    (comp (ref "SW_R")
      (value "TL3315NF100Q")
      (footprint "eagle-import:TL3315NF100Q")
      (fields
        (field (name "MANUFACTURER") "E-Switch")
        (field (name "DIGIKEY_PARTNO") "EG4620TR-ND")
        (field (name "VENDOR") "Digikey")
        (field (name "VPN") "EG4620CT-ND")
        (field (name "CREATED_BY") "PCBLayout.com")
      )
      (libsource (lib "eagle-import") (part "TL3315NF100Q"))
    )
    (comp (ref "SW_S")
      (value "TL3315NF100Q")
      (footprint "eagle-import:TL3315NF100Q")
      (fields
        (field (name "MANUFACTURER") "E-Switch")
        (field (name "DIGIKEY_PARTNO") "EG4620TR-ND")
        (field (name "VENDOR") "Digikey")
        (field (name "VPN") "EG4620CT-ND")
        (field (name "CREATED_BY") "PCBLayout.com")
      )
      (libsource (lib "eagle-import") (part "TL3315NF100Q"))
    )
    (comp (ref "SW_SHFT")
      (value "TL3315NF100Q")
      (footprint "eagle-import:TL3315NF100Q")
      (fields
        (field (name "MANUFACTURER") "E-Switch")
        (field (name "DIGIKEY_PARTNO") "EG4620TR-ND")
        (field (name "VENDOR") "Digikey")
        (field (name "VPN") "EG4620CT-ND")
        (field (name "CREATED_BY") "PCBLayout.com")
      )
      (libsource (lib "eagle-import") (part "TL3315NF100Q"))
    )
    (comp (ref "SW_SP1")
      (value "TL3315NF100Q")
      (footprint "eagle-import:TL3315NF100Q")
      (fields
        (field (name "MANUFACTURER") "E-Switch")
        (field (name "DIGIKEY_PARTNO") "EG4620TR-ND")
        (field (name "VENDOR") "Digikey")
        (field (name "VPN") "EG4620CT-ND")
        (field (name "CREATED_BY") "PCBLayout.com")
      )
      (libsource (lib "eagle-import") (part "TL3315NF100Q"))
    )
    (comp (ref "SW_SP2")
      (value "TL3315NF100Q")
      (footprint "eagle-import:TL3315NF100Q")
      (fields
        (field (name "MANUFACTURER") "E-Switch")
        (field (name "DIGIKEY_PARTNO") "EG4620TR-ND")
        (field (name "VENDOR") "Digikey")
        (field (name "VPN") "EG4620CT-ND")
        (field (name "CREATED_BY") "PCBLayout.com")
      )
      (libsource (lib "eagle-import") (part "TL3315NF100Q"))
    )
    (comp (ref "SW_SYM")
      (value "TL3315NF100Q")
      (footprint "eagle-import:TL3315NF100Q")
      (fields
        (field (name "MANUFACTURER") "E-Switch")
        (field (name "DIGIKEY_PARTNO") "EG4620TR-ND")
        (field (name "VENDOR") "Digikey")
        (field (name "VPN") "EG4620CT-ND")
        (field (name "CREATED_BY") "PCBLayout.com")
      )
      (libsource (lib "eagle-import") (part "TL3315NF100Q"))
    )
    (comp (ref "SW_T")
      (value "TL3315NF100Q")
      (footprint "eagle-import:TL3315NF100Q")
      (fields
        (field (name "MANUFACTURER") "E-Switch")
        (field (name "DIGIKEY_PARTNO") "EG4620TR-ND")
        (field (name "VENDOR") "Digikey")
        (field (name "VPN") "EG4620CT-ND")
        (field (name "CREATED_BY") "PCBLayout.com")
      )
      (libsource (lib "eagle-import") (part "TL3315NF100Q"))
    )
    (comp (ref "SW_TAB")
      (value "TL3315NF100Q")
      (footprint "eagle-import:TL3315NF100Q")
      (fields
        (field (name "MANUFACTURER") "E-Switch")
        (field (name "DIGIKEY_PARTNO") "EG4620TR-ND")
        (field (name "VENDOR") "Digikey")
        (field (name "VPN") "EG4620CT-ND")
        (field (name "CREATED_BY") "PCBLayout.com")
      )
      (libsource (lib "eagle-import") (part "TL3315NF100Q"))
    )
    (comp (ref "SW_U")
      (value "TL3315NF100Q")
      (footprint "eagle-import:TL3315NF100Q")
      (fields
        (field (name "MANUFACTURER") "E-Switch")
        (field (name "DIGIKEY_PARTNO") "EG4620TR-ND")
        (field (name "VENDOR") "Digikey")
        (field (name "VPN") "EG4620CT-ND")
        (field (name "CREATED_BY") "PCBLayout.com")
      )
      (libsource (lib "eagle-import") (part "TL3315NF100Q"))
    )
    (comp (ref "SW_V")
      (value "TL3315NF100Q")
      (footprint "eagle-import:TL3315NF100Q")
      (fields
        (field (name "MANUFACTURER") "E-Switch")
        (field (name "DIGIKEY_PARTNO") "EG4620TR-ND")
        (field (name "VENDOR") "Digikey")
        (field (name "VPN") "EG4620CT-ND")
        (field (name "CREATED_BY") "PCBLayout.com")
      )
      (libsource (lib "eagle-import") (part "TL3315NF100Q"))
    )
    (comp (ref "SW_W")
      (value "TL3315NF100Q")
      (footprint "eagle-import:TL3315NF100Q")
      (fields
        (field (name "MANUFACTURER") "E-Switch")
        (field (name "DIGIKEY_PARTNO") "EG4620TR-ND")
        (field (name "VENDOR") "Digikey")
        (field (name "VPN") "EG4620CT-ND")
        (field (name "CREATED_BY") "PCBLayout.com")
      )
      (libsource (lib "eagle-import") (part "TL3315NF100Q"))
    )
    (comp (ref "SW_X")
      (value "TL3315NF100Q")
      (footprint "eagle-import:TL3315NF100Q")
      (fields
        (field (name "MANUFACTURER") "E-Switch")
        (field (name "DIGIKEY_PARTNO") "EG4620TR-ND")
        (field (name "VENDOR") "Digikey")
        (field (name "VPN") "EG4620CT-ND")
        (field (name "CREATED_BY") "PCBLayout.com")
      )
      (libsource (lib "eagle-import") (part "TL3315NF100Q"))
    )
    (comp (ref "SW_Y")
      (value "TL3315NF100Q")
      (footprint "eagle-import:TL3315NF100Q")
      (fields
        (field (name "MANUFACTURER") "E-Switch")
        (field (name "DIGIKEY_PARTNO") "EG4620TR-ND")
        (field (name "VENDOR") "Digikey")
        (field (name "VPN") "EG4620CT-ND")
        (field (name "CREATED_BY") "PCBLayout.com")
      )
      (libsource (lib "eagle-import") (part "TL3315NF100Q"))
    )
    (comp (ref "SW_Z")
      (value "TL3315NF100Q")
      (footprint "eagle-import:TL3315NF100Q")
      (fields
        (field (name "MANUFACTURER") "E-Switch")
        (field (name "DIGIKEY_PARTNO") "EG4620TR-ND")
        (field (name "VENDOR") "Digikey")
        (field (name "VPN") "EG4620CT-ND")
        (field (name "CREATED_BY") "PCBLayout.com")
      )
      (libsource (lib "eagle-import") (part "TL3315NF100Q"))
    )
    (comp (ref "SW_}")
      (value "TL3315NF100Q")
      (footprint "eagle-import:TL3315NF100Q")
      (fields
        (field (name "MANUFACTURER") "E-Switch")
        (field (name "DIGIKEY_PARTNO") "EG4620TR-ND")
        (field (name "VENDOR") "Digikey")
        (field (name "VPN") "EG4620CT-ND")
        (field (name "CREATED_BY") "PCBLayout.com")
      )
      (libsource (lib "eagle-import") (part "TL3315NF100Q"))
    )
    (comp (ref "TP1")
      (value "TPB1,27")
      (footprint "eagle-import:B1,27")
      (libsource (lib "eagle-import") (part "TPB1,27"))
    )
    (comp (ref "TP2")
      (value "TPB1,27")
      (footprint "eagle-import:B1,27")
      (libsource (lib "eagle-import") (part "TPB1,27"))
    )
    (comp (ref "TP3")
      (value "TPB1,27")
      (footprint "eagle-import:B1,27")
      (libsource (lib "eagle-import") (part "TPB1,27"))
    )
    (comp (ref "TP4")
      (value "TPB1,27")
      (footprint "eagle-import:B1,27")
      (libsource (lib "eagle-import") (part "TPB1,27"))
    )
    (comp (ref "TP5")
      (value "TPB1,27")
      (footprint "eagle-import:B1,27")
      (libsource (lib "eagle-import") (part "TPB1,27"))
    )
    (comp (ref "TP6")
      (value "TPB1,27")
      (footprint "eagle-import:B1,27")
      (libsource (lib "eagle-import") (part "TPB1,27"))
    )
    (comp (ref "TP7")
      (value "TPB1,27")
      (footprint "eagle-import:B1,27")
      (libsource (lib "eagle-import") (part "TPB1,27"))
    )
    (comp (ref "TP8")
      (value "TPB1,27")
      (footprint "eagle-import:B1,27")
      (libsource (lib "eagle-import") (part "TPB1,27"))
    )
    (comp (ref "TP9")
      (value "TPB1,27")
      (footprint "eagle-import:B1,27")
      (libsource (lib "eagle-import") (part "TPB1,27"))
    )
    (comp (ref "TP10")
      (value "TPB1,27")
      (footprint "eagle-import:B1,27")
      (libsource (lib "eagle-import") (part "TPB1,27"))
    )
    (comp (ref "TP11")
      (value "TPB1,27")
      (footprint "eagle-import:B1,27")
      (libsource (lib "eagle-import") (part "TPB1,27"))
    )
    (comp (ref "TP12")
      (value "TPB1,27")
      (footprint "eagle-import:B1,27")
      (libsource (lib "eagle-import") (part "TPB1,27"))
    )
    (comp (ref "TP13")
      (value "TPB1,27")
      (footprint "eagle-import:B1,27")
      (libsource (lib "eagle-import") (part "TPB1,27"))
    )
    (comp (ref "TP14")
      (value "TPB1,27")
      (footprint "eagle-import:B1,27")
      (libsource (lib "eagle-import") (part "TPB1,27"))
    )
    (comp (ref "U$1")
      (value "CM0100000")
      (footprint "eagle-import:CM0")
      (fields (field (name "VENDOR") "EDATEC"))
      (libsource (lib "eagle-import") (part "CM0100000"))
    )
    (comp (ref "U2")
      (value "SC0914(13)")
      (footprint "eagle-import:QFN40P700X700X90-57N")
      (fields
        (field (name "MANUFACTURER") "Raspberry Pi")
        (field (name "VENDOR") "Digikey")
        (field (name "VPN") "2648-SC0914(13)CT-ND")
      )
      (libsource (lib "eagle-import") (part "SC0914(13)"))
    )
    (comp (ref "U3")
      (value "BQ25185DLHR")
      (footprint "eagle-import:IC_BQ25185DLHR")
      (fields
        (field (name "MANUFACTURER") "Texas Instruments")
        (field (name "VENDOR") "Digikey")
        (field (name "VPN") "296-BQ25185DLHRCT-ND")
        (field (name "CREATOR") "AMINA")
      )
      (libsource (lib "eagle-import") (part "BQ25185DLHR"))
    )
    (comp (ref "U4")
      (value "TPS61023DRLRDRL0006A")
      (footprint "eagle-import:DRL0006A")
      (fields
        (field (name "MANUFACTURER_PART_NUMBER") "TPS61023DRLR")
        (field (name "VENDOR") "Digikey")
        (field (name "VPN") "296-TPS61023DRLRCT-ND")
        (field (name "COPYRIGHT") "Copyright (C) 2026 Ultra Librarian. All rights reserved.")
      )
      (libsource (lib "eagle-import") (part "TPS61023DRLRDRL0006A"))
    )
    (comp (ref "U5")
      (value "FSUSB42MUX")
      (footprint "eagle-import:SOP50P490X110-10N")
      (fields
        (field (name "MANUFACTURER") "ON Semiconductor")
        (field (name "VENDOR") "Digikey")
        (field (name "VPN") "FSUSB42MUXCT-ND")
      )
      (libsource (lib "eagle-import") (part "FSUSB42MUX"))
    )
    (comp (ref "U6")
      (value "MAX17048G+T10")
      (footprint "eagle-import:SON50P200X200X80-9N")
      (fields (field (name "VENDOR") "Digikey") (field (name "VPN") "MAX17048G+T10CT-ND"))
      (libsource (lib "eagle-import") (part "MAX17048G+T10"))
    )
    (comp (ref "U7")
      (value "TLV320DAC3100IRHBR")
      (footprint "eagle-import:IC_ADS125H01IRHBT")
      (fields (field (name "VENDOR") "Digikey") (field (name "VPN") "296-27216-1-ND"))
      (libsource (lib "eagle-import") (part "TLV320DAC3100IRHBR"))
    )
    (comp (ref "U8")
      (value "W25Q32JVZPIQ")
      (footprint "eagle-import:SON127P600X500X80-9N")
      (fields
        (field (name "DIGIKEY_PART_NUMBER") "256-W25Q32JVZPIQ-TUBE-ND")
        (field (name "MF") "Winbond")
        (field (name "VENDOR") "Digikey")
        (field (name "VPN") "256-W25Q32JVZPIQ-TUBE-ND")
      )
      (libsource (lib "eagle-import") (part "W25Q32JVZPIQ"))
    )
    (comp (ref "Y1")
      (value "ABM8-272-T3")
      (footprint "eagle-import:XTAL_ABM8-272-T3")
      (fields
        (field (name "MANUFACTURER") "ABRACON")
        (field (name "VENDOR") "Digikey")
        (field (name "VPN") "535-ABM8-272-T3CT-ND")
        (field (name "CREATOR") "DIZAR")
      )
      (libsource (lib "eagle-import") (part "ABM8-272-T3"))
    )
  )
  (nets
    (net (code "1") (name "/SW") (class "Default")
      (node (ref "L1") (pin "2") (pinfunction "2_2") (pintype "passive"))
      (node (ref "U4") (pin "5") (pinfunction "SW_5") (pintype "power_in"))
    )
    (net (code "2") (name "/~{ACT_LED}") (class "Default")
      (node (ref "J4") (pin "4") (pinfunction "4_4") (pintype "passive"))
      (node (ref "U$1") (pin "P$118") (pinfunction "~{LED_NACT}_P$118") (pintype "bidirectional"))
    )
    (net (code "3") (name "/~{BAT_ALERT}") (class "Default")
      (node (ref "R17") (pin "1") (pinfunction "1_1") (pintype "passive"))
      (node (ref "U6") (pin "5") (pinfunction "~{ALERT}_5") (pintype "output"))
    )
    (net (code "4") (name "/~{RP2040_BOOT}") (class "Default")
      (node (ref "BOOT") (pin "1") (pinfunction "1_1") (pintype "passive"))
      (node (ref "BOOT") (pin "4") (pinfunction "1_4") (pintype "passive"))
      (node (ref "R3") (pin "1") (pinfunction "1_1") (pintype "passive"))
    )
    (net (code "5") (name "/~{RP2040_RESET}") (class "Default")
      (node (ref "R6") (pin "1") (pinfunction "1_1") (pintype "passive"))
      (node (ref "RESET") (pin "1") (pinfunction "1_1") (pintype "passive"))
      (node (ref "RESET") (pin "4") (pinfunction "1_4") (pintype "passive"))
      (node (ref "U2") (pin "26") (pinfunction "RUN_26") (pintype "input"))
    )
    (net (code "6") (name "/~{TOUCH_CS}") (class "Default")
      (node (ref "J4") (pin "8") (pinfunction "8_8") (pintype "passive"))
      (node (ref "U$1") (pin "P$89") (pinfunction "GPIO7_P$89") (pintype "bidirectional"))
    )
    (net (code "7") (name "/~{TOUCH_IRQ}") (class "Default")
      (node (ref "J4") (pin "7") (pinfunction "7_7") (pintype "passive"))
      (node (ref "U$1") (pin "P$98") (pinfunction "GPIO24_P$98") (pintype "bidirectional"))
    )
    (net (code "8") (name "1V1") (class "Default")
      (node (ref "C5") (pin "1") (pinfunction "1_1") (pintype "passive"))
      (node (ref "C6") (pin "1") (pinfunction "1_1") (pintype "passive"))
      (node (ref "C7") (pin "1") (pinfunction "1_1") (pintype "passive"))
      (node (ref "U2") (pin "23") (pinfunction "DVDD_23") (pintype "power_in"))
      (node (ref "U2") (pin "45") (pinfunction "VREG_VOUT_45") (pintype "output"))
      (node (ref "U2") (pin "50") (pinfunction "DVDD_50") (pintype "power_in"))
    )
    (net (code "9") (name "1V8") (class "Default")
      (node (ref "C27") (pin "1") (pinfunction "1_1") (pintype "passive"))
      (node (ref "C28") (pin "1") (pinfunction "1_1") (pintype "passive"))
      (node (ref "TP4") (pin "TP") (pinfunction "TP_TP") (pintype "input"))
      (node (ref "U$1") (pin "P$64") (pinfunction "CM0_1.8V_OUT_P$64") (pintype "power_in"))
      (node (ref "U$1") (pin "P$65") (pinfunction "CM0_1.8V_OUT_P$65") (pintype "power_in"))
      (node (ref "U7") (pin "3") (pinfunction "DVDD_3") (pintype "power_in"))
    )
    (net (code "10") (name "3V3") (class "Default")
      (node (ref "C1") (pin "1") (pinfunction "1_1") (pintype "passive"))
      (node (ref "C10") (pin "1") (pinfunction "1_1") (pintype "passive"))
      (node (ref "C11") (pin "1") (pinfunction "1_1") (pintype "passive"))
      (node (ref "C12") (pin "1") (pinfunction "1_1") (pintype "passive"))
      (node (ref "C13") (pin "1") (pinfunction "1_1") (pintype "passive"))
      (node (ref "C14") (pin "1") (pinfunction "1_1") (pintype "passive"))
      (node (ref "C26") (pin "1") (pinfunction "1_1") (pintype "passive"))
      (node (ref "C30") (pin "1") (pinfunction "1_1") (pintype "passive"))
      (node (ref "C31") (pin "1") (pinfunction "1_1") (pintype "passive"))
      (node (ref "C4") (pin "1") (pinfunction "1_1") (pintype "passive"))
      (node (ref "C8") (pin "1") (pinfunction "1_1") (pintype "passive"))
      (node (ref "C9") (pin "1") (pinfunction "1_1") (pintype "passive"))
      (node (ref "J3") (pin "4") (pinfunction "VDD_4") (pintype "power_in"))
      (node (ref "J4") (pin "3") (pinfunction "3_3") (pintype "passive"))
      (node (ref "R1") (pin "2") (pinfunction "2_2") (pintype "passive"))
      (node (ref "R17") (pin "2") (pinfunction "2_2") (pintype "passive"))
      (node (ref "R21") (pin "2") (pinfunction "2_2") (pintype "passive"))
      (node (ref "R6") (pin "2") (pinfunction "2_2") (pintype "passive"))
      (node (ref "R7") (pin "2") (pinfunction "2_2") (pintype "passive"))
      (node (ref "R8") (pin "2") (pinfunction "2_2") (pintype "passive"))
      (node (ref "TP3") (pin "TP") (pinfunction "TP_TP") (pintype "input"))
      (node (ref "U$1") (pin "P$119") (pinfunction "CM0_3.3V_OUT_P$119") (pintype "power_in"))
      (node (ref "U$1") (pin "P$120") (pinfunction "VREF_GPIO_P$120") (pintype "bidirectional"))
      (node (ref "U$1") (pin "P$122") (pinfunction "SD_VREF_P$122") (pintype "bidirectional"))
      (node (ref "U$1") (pin "P$41") (pinfunction "CM0_3.3V_OUT_P$41") (pintype "power_in"))
      (node (ref "U2") (pin "1") (pinfunction "IOVDD_1") (pintype "power_in"))
      (node (ref "U2") (pin "10") (pinfunction "IOVDD_10") (pintype "power_in"))
      (node (ref "U2") (pin "22") (pinfunction "IOVDD_22") (pintype "power_in"))
      (node (ref "U2") (pin "33") (pinfunction "IOVDD_33") (pintype "power_in"))
      (node (ref "U2") (pin "42") (pinfunction "IOVDD_42") (pintype "power_in"))
      (node (ref "U2") (pin "43") (pinfunction "ADC_AVDD_43") (pintype "power_in"))
      (node (ref "U2") (pin "44") (pinfunction "VREG_VIN_44") (pintype "input"))
      (node (ref "U2") (pin "48") (pinfunction "USB_VDD_48") (pintype "power_in"))
      (node (ref "U2") (pin "49") (pinfunction "IOVDD_49") (pintype "power_in"))
      (node (ref "U5") (pin "1") (pinfunction "VCC_1") (pintype "power_in"))
      (node (ref "U7") (pin "17") (pinfunction "AVDD_17") (pintype "power_in"))
      (node (ref "U7") (pin "2") (pinfunction "IOVDD_2") (pintype "power_in"))
      (node (ref "U7") (pin "28") (pinfunction "HPVDD_28") (pintype "power_in"))
      (node (ref "U8") (pin "8") (pinfunction "VCC_8") (pintype "power_in"))
    )
    (net (code "11") (name "5V") (class "Default")
      (node (ref "C18") (pin "1") (pinfunction "1_1") (pintype "passive"))
      (node (ref "C19") (pin "1") (pinfunction "1_1") (pintype "passive"))
      (node (ref "C29") (pin "1") (pinfunction "1_1") (pintype "passive"))
      (node (ref "C32") (pin "1") (pinfunction "1_1") (pintype "passive"))
      (node (ref "J4") (pin "5") (pinfunction "5_5") (pintype "passive"))
      (node (ref "R15") (pin "2") (pinfunction "2_2") (pintype "passive"))
      (node (ref "TP1") (pin "TP") (pinfunction "TP_TP") (pintype "input"))
      (node (ref "U$1") (pin "P$67") (pinfunction "5V_IN_P$67") (pintype "power_in"))
      (node (ref "U$1") (pin "P$68") (pinfunction "5V_IN_P$68") (pintype "power_in"))
      (node (ref "U4") (pin "6") (pinfunction "VOUT_6") (pintype "power_in"))
      (node (ref "U7") (pin "21") (pinfunction "SPKVDD_21") (pintype "power_in"))
      (node (ref "U7") (pin "24") (pinfunction "SPKVDD_24") (pintype "power_in"))
    )
    (net (code "12") (name "CM0_USB_N") (class "Default")
      (node (ref "U$1") (pin "P$35") (pinfunction "USB_N_P$35") (pintype "bidirectional"))
      (node (ref "U5") (pin "6") (pinfunction "HSD1-_6") (pintype "bidirectional"))
    )
    (net (code "13") (name "CM0_USB_P") (class "Default")
      (node (ref "U$1") (pin "P$36") (pinfunction "USB_P_P$36") (pintype "bidirectional"))
      (node (ref "U5") (pin "7") (pinfunction "HSD1+_7") (pintype "bidirectional"))
    )
    (net (code "14") (name "COL0") (class "Default")
      (node (ref "SW_A") (pin "1") (pinfunction "1_1") (pintype "passive"))
      (node (ref "SW_A") (pin "2") (pinfunction "2_2") (pintype "passive"))
      (node (ref "SW_CTL") (pin "1") (pinfunction "1_1") (pintype "passive"))
      (node (ref "SW_CTL") (pin "2") (pinfunction "2_2") (pintype "passive"))
      (node (ref "SW_Q") (pin "1") (pinfunction "1_1") (pintype "passive"))
      (node (ref "SW_Q") (pin "2") (pinfunction "2_2") (pintype "passive"))
      (node (ref "SW_Z") (pin "1") (pinfunction "1_1") (pintype "passive"))
      (node (ref "SW_Z") (pin "2") (pinfunction "2_2") (pintype "passive"))
      (node (ref "U2") (pin "18") (pinfunction "GPIO15_18") (pintype "bidirectional"))
    )
    (net (code "15") (name "COL1") (class "Default")
      (node (ref "SW_ALT") (pin "1") (pinfunction "1_1") (pintype "passive"))
      (node (ref "SW_ALT") (pin "2") (pinfunction "2_2") (pintype "passive"))
      (node (ref "SW_S") (pin "1") (pinfunction "1_1") (pintype "passive"))
      (node (ref "SW_S") (pin "2") (pinfunction "2_2") (pintype "passive"))
      (node (ref "SW_W") (pin "1") (pinfunction "1_1") (pintype "passive"))
      (node (ref "SW_W") (pin "2") (pinfunction "2_2") (pintype "passive"))
      (node (ref "SW_X") (pin "1") (pinfunction "1_1") (pintype "passive"))
      (node (ref "SW_X") (pin "2") (pinfunction "2_2") (pintype "passive"))
      (node (ref "U2") (pin "27") (pinfunction "GPIO16_27") (pintype "bidirectional"))
    )
    (net (code "16") (name "COL2") (class "Default")
      (node (ref "SW_C") (pin "1") (pinfunction "1_1") (pintype "passive"))
      (node (ref "SW_C") (pin "2") (pinfunction "2_2") (pintype "passive"))
      (node (ref "SW_CMD") (pin "1") (pinfunction "1_1") (pintype "passive"))
      (node (ref "SW_CMD") (pin "2") (pinfunction "2_2") (pintype "passive"))
      (node (ref "SW_D") (pin "1") (pinfunction "1_1") (pintype "passive"))
      (node (ref "SW_D") (pin "2") (pinfunction "2_2") (pintype "passive"))
      (node (ref "SW_E") (pin "1") (pinfunction "1_1") (pintype "passive"))
      (node (ref "SW_E") (pin "2") (pinfunction "2_2") (pintype "passive"))
      (node (ref "U2") (pin "28") (pinfunction "GPIO17_28") (pintype "bidirectional"))
    )
    (net (code "17") (name "COL3") (class "Default")
      (node (ref "SW_F") (pin "1") (pinfunction "1_1") (pintype "passive"))
      (node (ref "SW_F") (pin "2") (pinfunction "2_2") (pintype "passive"))
      (node (ref "SW_R") (pin "1") (pinfunction "1_1") (pintype "passive"))
      (node (ref "SW_R") (pin "2") (pinfunction "2_2") (pintype "passive"))
      (node (ref "SW_SP1") (pin "1") (pinfunction "1_1") (pintype "passive"))
      (node (ref "SW_SP1") (pin "2") (pinfunction "2_2") (pintype "passive"))
      (node (ref "SW_V") (pin "1") (pinfunction "1_1") (pintype "passive"))
      (node (ref "SW_V") (pin "2") (pinfunction "2_2") (pintype "passive"))
      (node (ref "U2") (pin "29") (pinfunction "GPIO18_29") (pintype "bidirectional"))
    )
    (net (code "18") (name "COL4") (class "Default")
      (node (ref "SW_B") (pin "1") (pinfunction "1_1") (pintype "passive"))
      (node (ref "SW_B") (pin "2") (pinfunction "2_2") (pintype "passive"))
      (node (ref "SW_G") (pin "1") (pinfunction "1_1") (pintype "passive"))
      (node (ref "SW_G") (pin "2") (pinfunction "2_2") (pintype "passive"))
      (node (ref "SW_SP2") (pin "1") (pinfunction "1_1") (pintype "passive"))
      (node (ref "SW_SP2") (pin "2") (pinfunction "2_2") (pintype "passive"))
      (node (ref "SW_T") (pin "1") (pinfunction "1_1") (pintype "passive"))
      (node (ref "SW_T") (pin "2") (pinfunction "2_2") (pintype "passive"))
      (node (ref "U2") (pin "30") (pinfunction "GPIO19_30") (pintype "bidirectional"))
    )
    (net (code "19") (name "COL5") (class "Default")
      (node (ref "SW_H") (pin "1") (pinfunction "1_1") (pintype "passive"))
      (node (ref "SW_H") (pin "2") (pinfunction "2_2") (pintype "passive"))
      (node (ref "SW_N") (pin "1") (pinfunction "1_1") (pintype "passive"))
      (node (ref "SW_N") (pin "2") (pinfunction "2_2") (pintype "passive"))
      (node (ref "SW_SYM") (pin "1") (pinfunction "1_1") (pintype "passive"))
      (node (ref "SW_SYM") (pin "2") (pinfunction "2_2") (pintype "passive"))
      (node (ref "SW_Y") (pin "1") (pinfunction "1_1") (pintype "passive"))
      (node (ref "SW_Y") (pin "2") (pinfunction "2_2") (pintype "passive"))
      (node (ref "U2") (pin "31") (pinfunction "GPIO20_31") (pintype "bidirectional"))
    )
    (net (code "20") (name "COL6") (class "Default")
      (node (ref "SW_J") (pin "1") (pinfunction "1_1") (pintype "passive"))
      (node (ref "SW_J") (pin "2") (pinfunction "2_2") (pintype "passive"))
      (node (ref "SW_M") (pin "1") (pinfunction "1_1") (pintype "passive"))
      (node (ref "SW_M") (pin "2") (pinfunction "2_2") (pintype "passive"))
      (node (ref "SW_TAB") (pin "1") (pinfunction "1_1") (pintype "passive"))
      (node (ref "SW_TAB") (pin "2") (pinfunction "2_2") (pintype "passive"))
      (node (ref "SW_U") (pin "1") (pinfunction "1_1") (pintype "passive"))
      (node (ref "SW_U") (pin "2") (pinfunction "2_2") (pintype "passive"))
      (node (ref "U2") (pin "32") (pinfunction "GPIO21_32") (pintype "bidirectional"))
    )
    (net (code "21") (name "COL7") (class "Default")
      (node (ref "SW_.") (pin "1") (pinfunction "1_1") (pintype "passive"))
      (node (ref "SW_.") (pin "2") (pinfunction "2_2") (pintype "passive"))
      (node (ref "SW_I") (pin "1") (pinfunction "1_1") (pintype "passive"))
      (node (ref "SW_I") (pin "2") (pinfunction "2_2") (pintype "passive"))
      (node (ref "SW_K") (pin "1") (pinfunction "1_1") (pintype "passive"))
      (node (ref "SW_K") (pin "2") (pinfunction "2_2") (pintype "passive"))
      (node (ref "SW_SHFT") (pin "1") (pinfunction "1_1") (pintype "passive"))
      (node (ref "SW_SHFT") (pin "2") (pinfunction "2_2") (pintype "passive"))
      (node (ref "U2") (pin "34") (pinfunction "GPIO22_34") (pintype "bidirectional"))
    )
    (net (code "22") (name "COL8") (class "Default")
      (node (ref "SW_/") (pin "1") (pinfunction "1_1") (pintype "passive"))
      (node (ref "SW_/") (pin "2") (pinfunction "2_2") (pintype "passive"))
      (node (ref "SW_?") (pin "1") (pinfunction "1_1") (pintype "passive"))
      (node (ref "SW_?") (pin "2") (pinfunction "2_2") (pintype "passive"))
      (node (ref "SW_L") (pin "1") (pinfunction "1_1") (pintype "passive"))
      (node (ref "SW_L") (pin "2") (pinfunction "2_2") (pintype "passive"))
      (node (ref "SW_O") (pin "1") (pinfunction "1_1") (pintype "passive"))
      (node (ref "SW_O") (pin "2") (pinfunction "2_2") (pintype "passive"))
      (node (ref "U2") (pin "35") (pinfunction "GPIO23_35") (pintype "bidirectional"))
    )
    (net (code "23") (name "COL9") (class "Default")
      (node (ref "SW_BSP") (pin "1") (pinfunction "1_1") (pintype "passive"))
      (node (ref "SW_BSP") (pin "2") (pinfunction "2_2") (pintype "passive"))
      (node (ref "SW_ENTER") (pin "1") (pinfunction "1_1") (pintype "passive"))
      (node (ref "SW_ENTER") (pin "2") (pinfunction "2_2") (pintype "passive"))
      (node (ref "SW_P") (pin "1") (pinfunction "1_1") (pintype "passive"))
      (node (ref "SW_P") (pin "2") (pinfunction "2_2") (pintype "passive"))
      (node (ref "SW_}") (pin "1") (pinfunction "1_1") (pintype "passive"))
      (node (ref "SW_}") (pin "2") (pinfunction "2_2") (pintype "passive"))
      (node (ref "U2") (pin "36") (pinfunction "GPIO24_36") (pintype "bidirectional"))
    )
    (net (code "24") (name "DAC_BCLK") (class "Default")
      (node (ref "U$1") (pin "P$105") (pinfunction "GPIO18_P$105") (pintype "bidirectional"))
      (node (ref "U7") (pin "7") (pinfunction "BCLK_7") (pintype "input"))
    )
    (net (code "25") (name "DAC_DIN") (class "Default")
      (node (ref "U$1") (pin "P$73") (pinfunction "GPIO21_P$73") (pintype "bidirectional"))
      (node (ref "U7") (pin "5") (pinfunction "DIN_5") (pintype "input"))
    )
    (net (code "26") (name "DAC_GPIO") (class "Default")
      (node (ref "U$1") (pin "P$74") (pinfunction "GPIO20_P$74") (pintype "bidirectional"))
      (node (ref "U7") (pin "32") (pinfunction "GPIO1_32") (pintype "bidirectional"))
    )
    (net (code "27") (name "DAC_WCLK") (class "Default")
      (node (ref "U$1") (pin "P$79") (pinfunction "GPIO19_P$79") (pintype "bidirectional"))
      (node (ref "U7") (pin "6") (pinfunction "WCLK_6") (pintype "input"))
    )
    (net (code "28") (name "DISPLAY_BL") (class "Default")
      (node (ref "J4") (pin "9") (pinfunction "9_9") (pintype "passive"))
      (node (ref "U$1") (pin "P$82") (pinfunction "GPIO12_P$82") (pintype "bidirectional"))
    )
    (net (code "29") (name "DISPLAY_CS") (class "Default")
      (node (ref "J4") (pin "11") (pinfunction "11_11") (pintype "passive"))
      (node (ref "U$1") (pin "P$91") (pinfunction "GPIO8_P$91") (pintype "bidirectional"))
    )
    (net (code "30") (name "DISPLAY_DC") (class "Default")
      (node (ref "J4") (pin "10") (pinfunction "10_10") (pintype "passive"))
      (node (ref "U$1") (pin "P$94") (pinfunction "GPIO25_P$94") (pintype "bidirectional"))
    )
    (net (code "31") (name "DPAD_DOWN") (class "Default")
      (node (ref "GPAD_D") (pin "1") (pinfunction "1_1") (pintype "passive"))
      (node (ref "GPAD_D") (pin "2") (pinfunction "2_2") (pintype "passive"))
      (node (ref "U2") (pin "5") (pinfunction "GPIO3_5") (pintype "bidirectional"))
    )
    (net (code "32") (name "DPAD_LEFT") (class "Default")
      (node (ref "GPAD_L") (pin "1") (pinfunction "1_1") (pintype "passive"))
      (node (ref "GPAD_L") (pin "2") (pinfunction "2_2") (pintype "passive"))
      (node (ref "U2") (pin "3") (pinfunction "GPIO1_3") (pintype "bidirectional"))
    )
    (net (code "33") (name "DPAD_RIGHT") (class "Default")
      (node (ref "GPAD_R") (pin "1") (pinfunction "1_1") (pintype "passive"))
      (node (ref "GPAD_R") (pin "2") (pinfunction "2_2") (pintype "passive"))
      (node (ref "U2") (pin "4") (pinfunction "GPIO2_4") (pintype "bidirectional"))
    )
    (net (code "34") (name "DPAD_UP") (class "Default")
      (node (ref "GPAD_U") (pin "1") (pinfunction "1_1") (pintype "passive"))
      (node (ref "GPAD_U") (pin "2") (pinfunction "2_2") (pintype "passive"))
      (node (ref "U2") (pin "2") (pinfunction "GPIO0_2") (pintype "bidirectional"))
    )
    (net (code "35") (name "GND") (class "Default")
      (node (ref "BAT") (pin "2") (pinfunction "2_2") (pintype "passive"))
      (node (ref "BOOT") (pin "2") (pinfunction "2_2") (pintype "passive"))
      (node (ref "BOOT") (pin "3") (pinfunction "2_3") (pintype "passive"))
      (node (ref "C1") (pin "2") (pinfunction "2_2") (pintype "passive"))
      (node (ref "C10") (pin "2") (pinfunction "2_2") (pintype "passive"))
      (node (ref "C11") (pin "2") (pinfunction "2_2") (pintype "passive"))
      (node (ref "C12") (pin "2") (pinfunction "2_2") (pintype "passive"))
      (node (ref "C13") (pin "2") (pinfunction "2_2") (pintype "passive"))
      (node (ref "C14") (pin "2") (pinfunction "2_2") (pintype "passive"))
      (node (ref "C15") (pin "2") (pinfunction "2_2") (pintype "passive"))
      (node (ref "C16") (pin "2") (pinfunction "2_2") (pintype "passive"))
      (node (ref "C17") (pin "2") (pinfunction "2_2") (pintype "passive"))
      (node (ref "C18") (pin "2") (pinfunction "2_2") (pintype "passive"))
      (node (ref "C19") (pin "2") (pinfunction "2_2") (pintype "passive"))
      (node (ref "C2") (pin "1") (pinfunction "1_1") (pintype "passive"))
      (node (ref "C20") (pin "2") (pinfunction "2_2") (pintype "passive"))
      (node (ref "C21") (pin "2") (pinfunction "2_2") (pintype "passive"))
      (node (ref "C25") (pin "2") (pinfunction "2_2") (pintype "passive"))
      (node (ref "C26") (pin "2") (pinfunction "2_2") (pintype "passive"))
      (node (ref "C27") (pin "2") (pinfunction "2_2") (pintype "passive"))
      (node (ref "C28") (pin "2") (pinfunction "2_2") (pintype "passive"))
      (node (ref "C29") (pin "2") (pinfunction "2_2") (pintype "passive"))
      (node (ref "C3") (pin "1") (pinfunction "1_1") (pintype "passive"))
      (node (ref "C30") (pin "2") (pinfunction "2_2") (pintype "passive"))
      (node (ref "C31") (pin "2") (pinfunction "2_2") (pintype "passive"))
      (node (ref "C32") (pin "2") (pinfunction "2_2") (pintype "passive"))
      (node (ref "C33") (pin "2") (pinfunction "2_2") (pintype "passive"))
      (node (ref "C4") (pin "2") (pinfunction "2_2") (pintype "passive"))
      (node (ref "C5") (pin "2") (pinfunction "2_2") (pintype "passive"))
      (node (ref "C6") (pin "2") (pinfunction "2_2") (pintype "passive"))
      (node (ref "C7") (pin "2") (pinfunction "2_2") (pintype "passive"))
      (node (ref "C8") (pin "2") (pinfunction "2_2") (pintype "passive"))
      (node (ref "C9") (pin "2") (pinfunction "2_2") (pintype "passive"))
      (node (ref "GPAD_A") (pin "3") (pinfunction "3_3") (pintype "passive"))
      (node (ref "GPAD_A") (pin "4") (pinfunction "4_4") (pintype "passive"))
      (node (ref "GPAD_B") (pin "3") (pinfunction "3_3") (pintype "passive"))
      (node (ref "GPAD_B") (pin "4") (pinfunction "4_4") (pintype "passive"))
      (node (ref "GPAD_D") (pin "3") (pinfunction "3_3") (pintype "passive"))
      (node (ref "GPAD_D") (pin "4") (pinfunction "4_4") (pintype "passive"))
      (node (ref "GPAD_L") (pin "3") (pinfunction "3_3") (pintype "passive"))
      (node (ref "GPAD_L") (pin "4") (pinfunction "4_4") (pintype "passive"))
      (node (ref "GPAD_R") (pin "3") (pinfunction "3_3") (pintype "passive"))
      (node (ref "GPAD_R") (pin "4") (pinfunction "4_4") (pintype "passive"))
      (node (ref "GPAD_U") (pin "3") (pinfunction "3_3") (pintype "passive"))
      (node (ref "GPAD_U") (pin "4") (pinfunction "4_4") (pintype "passive"))
      (node (ref "GPAD_X") (pin "3") (pinfunction "3_3") (pintype "passive"))
      (node (ref "GPAD_X") (pin "4") (pinfunction "4_4") (pintype "passive"))
      (node (ref "GPAD_Y") (pin "3") (pinfunction "3_3") (pintype "passive"))
      (node (ref "GPAD_Y") (pin "4") (pinfunction "4_4") (pintype "passive"))
      (node (ref "J2") (pin "2") (pinfunction "2_2") (pintype "passive"))
      (node (ref "J3") (pin "6") (pinfunction "VSS_6") (pintype "power_in"))
      (node (ref "J3") (pin "G1") (pinfunction "COVER_GND_G1") (pintype "power_in"))
      (node (ref "J3") (pin "G2") (pinfunction "COVER_GND_G2") (pintype "power_in"))
      (node (ref "J3") (pin "G3") (pinfunction "COVER_GND_G3") (pintype "power_in"))
      (node (ref "J3") (pin "G4") (pinfunction "COVER_GND_G4") (pintype "power_in"))
      (node (ref "J4") (pin "1") (pinfunction "1_1") (pintype "passive"))
      (node (ref "J4") (pin "15") (pinfunction "15_15") (pintype "passive"))
      (node (ref "J4") (pin "16") (pinfunction "16_16") (pintype "passive"))
      (node (ref "J4") (pin "2") (pinfunction "2_2") (pintype "passive"))
      (node (ref "J5") (pin "A12_B1") (pinfunction "GND_A12_B1") (pintype "passive"))
      (node (ref "J5") (pin "A1_B12") (pinfunction "GND_A1_B12") (pintype "passive"))
      (node (ref "J5") (pin "SH1") (pinfunction "SHIELD_SH1") (pintype "passive"))
      (node (ref "J5") (pin "SH2") (pinfunction "SHIELD_SH2") (pintype "passive"))
      (node (ref "J5") (pin "SH3") (pinfunction "SHIELD_SH3") (pintype "passive"))
      (node (ref "J5") (pin "SH4") (pinfunction "SHIELD_SH4") (pintype "passive"))
      (node (ref "JP1") (pin "1") (pinfunction "1_1") (pintype "passive"))
      (node (ref "Q2") (pin "2") (pinfunction "S_2") (pintype "passive"))
      (node (ref "R12") (pin "1") (pinfunction "1_1") (pintype "passive"))
      (node (ref "R13") (pin "1") (pinfunction "1_1") (pintype "passive"))
      (node (ref "R14") (pin "1") (pinfunction "1_1") (pintype "passive"))
      (node (ref "R16") (pin "1") (pinfunction "1_1") (pintype "passive"))
      (node (ref "R19") (pin "2") (pinfunction "2_2") (pintype "passive"))
      (node (ref "R20") (pin "1") (pinfunction "1_1") (pintype "passive"))
      (node (ref "R24") (pin "1") (pinfunction "1_1") (pintype "passive"))
      (node (ref "R27") (pin "2") (pinfunction "2_2") (pintype "passive"))
      (node (ref "RESET") (pin "2") (pinfunction "2_2") (pintype "passive"))
      (node (ref "RESET") (pin "3") (pinfunction "2_3") (pintype "passive"))
      (node (ref "SELECT") (pin "3") (pinfunction "3_3") (pintype "passive"))
      (node (ref "SELECT") (pin "4") (pinfunction "4_4") (pintype "passive"))
      (node (ref "START") (pin "3") (pinfunction "3_3") (pintype "passive"))
      (node (ref "START") (pin "4") (pinfunction "4_4") (pintype "passive"))
      (node (ref "TP12") (pin "TP") (pinfunction "TP_TP") (pintype "input"))
      (node (ref "TP13") (pin "TP") (pinfunction "TP_TP") (pintype "input"))
      (node (ref "TP14") (pin "TP") (pinfunction "TP_TP") (pintype "input"))
      (node (ref "TP2") (pin "TP") (pinfunction "TP_TP") (pintype "input"))
      (node (ref "U$1") (pin "P$1") (pinfunction "GND_P$1") (pintype "power_in"))
      (node (ref "U$1") (pin "P$10") (pinfunction "GND_P$10") (pintype "power_in"))
      (node (ref "U$1") (pin "P$100") (pinfunction "GND_P$100") (pintype "power_in"))
      (node (ref "U$1") (pin "P$103") (pinfunction "GND_P$103") (pintype "power_in"))
      (node (ref "U$1") (pin "P$106") (pinfunction "GND_P$106") (pintype "power_in"))
      (node (ref "U$1") (pin "P$109") (pinfunction "GND_P$109") (pintype "power_in"))
      (node (ref "U$1") (pin "P$112") (pinfunction "GND_P$112") (pintype "power_in"))
      (node (ref "U$1") (pin "P$115") (pinfunction "GND_P$115") (pintype "power_in"))
      (node (ref "U$1") (pin "P$123") (pinfunction "GND_P$123") (pintype "power_in"))
      (node (ref "U$1") (pin "P$126") (pinfunction "GND_P$126") (pintype "power_in"))
      (node (ref "U$1") (pin "P$129") (pinfunction "GND_P$129") (pintype "power_in"))
      (node (ref "U$1") (pin "P$13") (pinfunction "GND_P$13") (pintype "power_in"))
      (node (ref "U$1") (pin "P$132") (pinfunction "GND_P$132") (pintype "power_in"))
      (node (ref "U$1") (pin "P$16") (pinfunction "GND_P$16") (pintype "power_in"))
      (node (ref "U$1") (pin "P$21") (pinfunction "GND_P$21") (pintype "power_in"))
      (node (ref "U$1") (pin "P$24") (pinfunction "GND_P$24") (pintype "power_in"))
      (node (ref "U$1") (pin "P$27") (pinfunction "GND_P$27") (pintype "power_in"))
      (node (ref "U$1") (pin "P$30") (pinfunction "GND_P$30") (pintype "power_in"))
      (node (ref "U$1") (pin "P$33") (pinfunction "GND_P$33") (pintype "power_in"))
      (node (ref "U$1") (pin "P$34") (pinfunction "GND_P$34") (pintype "power_in"))
      (node (ref "U$1") (pin "P$37") (pinfunction "GND_P$37") (pintype "power_in"))
      (node (ref "U$1") (pin "P$4") (pinfunction "GND_P$4") (pintype "power_in"))
      (node (ref "U$1") (pin "P$40") (pinfunction "GND_P$40") (pintype "power_in"))
      (node (ref "U$1") (pin "P$45") (pinfunction "GND_P$45") (pintype "power_in"))
      (node (ref "U$1") (pin "P$48") (pinfunction "GND_P$48") (pintype "power_in"))
      (node (ref "U$1") (pin "P$51") (pinfunction "GND_P$51") (pintype "power_in"))
      (node (ref "U$1") (pin "P$54") (pinfunction "GND_P$54") (pintype "power_in"))
      (node (ref "U$1") (pin "P$57") (pinfunction "GND_P$57") (pintype "power_in"))
      (node (ref "U$1") (pin "P$60") (pinfunction "GND_P$60") (pintype "power_in"))
      (node (ref "U$1") (pin "P$63") (pinfunction "GND_P$63") (pintype "power_in"))
      (node (ref "U$1") (pin "P$66") (pinfunction "GND_P$66") (pintype "power_in"))
      (node (ref "U$1") (pin "P$69") (pinfunction "GND_P$69") (pintype "power_in"))
      (node (ref "U$1") (pin "P$7") (pinfunction "GND_P$7") (pintype "power_in"))
      (node (ref "U$1") (pin "P$72") (pinfunction "GND_P$72") (pintype "power_in"))
      (node (ref "U$1") (pin "P$75") (pinfunction "GND_P$75") (pintype "power_in"))
      (node (ref "U$1") (pin "P$78") (pinfunction "GND_P$78") (pintype "power_in"))
      (node (ref "U$1") (pin "P$81") (pinfunction "GND_P$81") (pintype "power_in"))
      (node (ref "U$1") (pin "P$84") (pinfunction "GND_P$84") (pintype "power_in"))
      (node (ref "U$1") (pin "P$87") (pinfunction "GND_P$87") (pintype "power_in"))
      (node (ref "U$1") (pin "P$90") (pinfunction "GND_P$90") (pintype "power_in"))
      (node (ref "U$1") (pin "P$93") (pinfunction "GND_P$93") (pintype "power_in"))
      (node (ref "U$1") (pin "P$96") (pinfunction "GND_P$96") (pintype "power_in"))
      (node (ref "U$1") (pin "P$99") (pinfunction "GND_P$99") (pintype "power_in"))
      (node (ref "U2") (pin "19") (pinfunction "TESTEN_19") (pintype "passive"))
      (node (ref "U2") (pin "57") (pinfunction "GND_57") (pintype "power_in"))
      (node (ref "U3") (pin "11") (pinfunction "THERMAL_PAD_11") (pintype "passive"))
      (node (ref "U3") (pin "12") (pinfunction "THERMAL_PAD_12") (pintype "passive"))
      (node (ref "U3") (pin "13") (pinfunction "THERMAL_PAD_13") (pintype "passive"))
      (node (ref "U3") (pin "4") (pinfunction "~{CE}_4") (pintype "input"))
      (node (ref "U3") (pin "5") (pinfunction "GND_5") (pintype "power_in"))
      (node (ref "U4") (pin "4") (pinfunction "GND_4") (pintype "power_in"))
      (node (ref "U5") (pin "10") (pinfunction "~{OE}_10") (pintype "input"))
      (node (ref "U5") (pin "5") (pinfunction "GND_5") (pintype "power_in"))
      (node (ref "U6") (pin "1") (pinfunction "CTG_1") (pintype "power_in"))
      (node (ref "U6") (pin "4") (pinfunction "GND_4") (pintype "power_in"))
      (node (ref "U6") (pin "6") (pinfunction "QSTRT_6") (pintype "input"))
      (node (ref "U6") (pin "9") (pinfunction "EP_9") (pintype "power_in"))
      (node (ref "U7") (pin "1") (pinfunction "IOVSS_1") (pintype "power_in"))
      (node (ref "U7") (pin "16") (pinfunction "AVSS_16") (pintype "power_in"))
      (node (ref "U7") (pin "18") (pinfunction "DVSS_18") (pintype "power_in"))
      (node (ref "U7") (pin "20") (pinfunction "SPKVSS_20") (pintype "power_in"))
      (node (ref "U7") (pin "25") (pinfunction "SPKVSS_25") (pintype "power_in"))
      (node (ref "U7") (pin "29") (pinfunction "HPVSS_29") (pintype "power_in"))
      (node (ref "U7") (pin "33") (pinfunction "EP_33") (pintype "bidirectional"))
      (node (ref "U7") (pin "34") (pinfunction "EP_34") (pintype "bidirectional"))
      (node (ref "U7") (pin "35") (pinfunction "EP_35") (pintype "bidirectional"))
      (node (ref "U7") (pin "36") (pinfunction "EP_36") (pintype "bidirectional"))
      (node (ref "U7") (pin "37") (pinfunction "EP_37") (pintype "bidirectional"))
      (node (ref "U7") (pin "38") (pinfunction "EP_38") (pintype "bidirectional"))
      (node (ref "U8") (pin "4") (pinfunction "GND_4") (pintype "power_in"))
      (node (ref "U8") (pin "9") (pinfunction "EXP_9") (pintype "passive"))
      (node (ref "Y1") (pin "2") (pinfunction "GND_2") (pintype "power_in"))
      (node (ref "Y1") (pin "4") (pinfunction "GND_4") (pintype "power_in"))
    )
    (net (code "36") (name "GPAD_A") (class "Default")
      (node (ref "GPAD_A") (pin "1") (pinfunction "1_1") (pintype "passive"))
      (node (ref "GPAD_A") (pin "2") (pinfunction "2_2") (pintype "passive"))
      (node (ref "U2") (pin "6") (pinfunction "GPIO4_6") (pintype "bidirectional"))
    )
    (net (code "37") (name "GPAD_B") (class "Default")
      (node (ref "GPAD_B") (pin "1") (pinfunction "1_1") (pintype "passive"))
      (node (ref "GPAD_B") (pin "2") (pinfunction "2_2") (pintype "passive"))
      (node (ref "U2") (pin "7") (pinfunction "GPIO5_7") (pintype "bidirectional"))
    )
    (net (code "38") (name "GPAD_X") (class "Default")
      (node (ref "GPAD_X") (pin "1") (pinfunction "1_1") (pintype "passive"))
      (node (ref "GPAD_X") (pin "2") (pinfunction "2_2") (pintype "passive"))
      (node (ref "U2") (pin "8") (pinfunction "GPIO6_8") (pintype "bidirectional"))
    )
    (net (code "39") (name "GPAD_Y") (class "Default")
      (node (ref "GPAD_Y") (pin "1") (pinfunction "1_1") (pintype "passive"))
      (node (ref "GPAD_Y") (pin "2") (pinfunction "2_2") (pintype "passive"))
      (node (ref "U2") (pin "9") (pinfunction "GPIO7_9") (pintype "bidirectional"))
    )
    (net (code "40") (name "HPL") (class "Default")
      (node (ref "C22") (pin "1") (pinfunction "1_1") (pintype "passive"))
      (node (ref "U7") (pin "27") (pinfunction "HPL_27") (pintype "output"))
    )
    (net (code "41") (name "HPR") (class "Default")
      (node (ref "C23") (pin "1") (pinfunction "1_1") (pintype "passive"))
      (node (ref "U7") (pin "30") (pinfunction "HPR_30") (pintype "output"))
    )
    (net (code "42") (name "MIC") (class "Default")
      (node (ref "J2") (pin "1") (pinfunction "1_1") (pintype "passive"))
      (node (ref "JP1") (pin "3") (pinfunction "3_3") (pintype "passive"))
      (node (ref "R22") (pin "2") (pinfunction "2_2") (pintype "passive"))
    )
    (net (code "43") (name "MICDET") (class "Default")
      (node (ref "JP1") (pin "2") (pinfunction "2_2") (pintype "passive"))
      (node (ref "U7") (pin "11") (pinfunction "VOL/MICDET_11") (pintype "input"))
    )
    (net (code "44") (name "Net-(C3-Pad2)") (class "Default")
      (node (ref "C3") (pin "2") (pinfunction "2_2") (pintype "passive"))
      (node (ref "R2") (pin "1") (pinfunction "1_1") (pintype "passive"))
      (node (ref "Y1") (pin "3") (pinfunction "3_3") (pintype "passive"))
    )
    (net (code "45") (name "Net-(D1-PadC)") (class "Default")
      (node (ref "D1") (pin "C") (pinfunction "C_C") (pintype "passive"))
      (node (ref "R10") (pin "1") (pinfunction "1_1") (pintype "passive"))
    )
    (net (code "46") (name "Net-(D2-PadC)") (class "Default")
      (node (ref "D2") (pin "C") (pinfunction "C_C") (pintype "passive"))
      (node (ref "R9") (pin "1") (pinfunction "1_1") (pintype "passive"))
    )
    (net (code "47") (name "Net-(D4-A)") (class "Default")
      (node (ref "C24") (pin "2") (pinfunction "2_2") (pintype "passive"))
      (node (ref "D4") (pin "2") (pinfunction "A_2") (pintype "passive"))
      (node (ref "Q1") (pin "1") (pinfunction "G_1") (pintype "passive"))
      (node (ref "Q2") (pin "3") (pinfunction "D_3") (pintype "passive"))
      (node (ref "R23") (pin "1") (pinfunction "1_1") (pintype "passive"))
    )
    (net (code "48") (name "Net-(D5-A)") (class "Default")
      (node (ref "D5") (pin "2") (pinfunction "A_2") (pintype "passive"))
      (node (ref "R26") (pin "2") (pinfunction "2_2") (pintype "passive"))
    )
    (net (code "49") (name "Net-(J5-CC1)") (class "Default")
      (node (ref "J5") (pin "A5") (pinfunction "CC1_A5") (pintype "passive"))
      (node (ref "R19") (pin "1") (pinfunction "1_1") (pintype "passive"))
    )
    (net (code "50") (name "Net-(J5-CC2)") (class "Default")
      (node (ref "J5") (pin "B5") (pinfunction "CC2_B5") (pintype "passive"))
      (node (ref "R20") (pin "2") (pinfunction "2_2") (pintype "passive"))
    )
    (net (code "51") (name "Net-(JP2-Pad2)") (class "Default")
      (node (ref "JP2") (pin "2") (pinfunction "2_2") (pintype "passive"))
      (node (ref "R28") (pin "2") (pinfunction "2_2") (pintype "passive"))
    )
    (net (code "52") (name "Net-(Q2-G)") (class "Default")
      (node (ref "C25") (pin "1") (pinfunction "1_1") (pintype "passive"))
      (node (ref "Q2") (pin "1") (pinfunction "G_1") (pintype "passive"))
      (node (ref "R24") (pin "2") (pinfunction "2_2") (pintype "passive"))
      (node (ref "R25") (pin "2") (pinfunction "2_2") (pintype "passive"))
    )
    (net (code "53") (name "Net-(U2-USB_DM)") (class "Default")
      (node (ref "R4") (pin "1") (pinfunction "1_1") (pintype "passive"))
      (node (ref "U2") (pin "46") (pinfunction "USB_DM_46") (pintype "bidirectional"))
    )
    (net (code "54") (name "Net-(U2-USB_DP)") (class "Default")
      (node (ref "R5") (pin "2") (pinfunction "2_2") (pintype "passive"))
      (node (ref "U2") (pin "47") (pinfunction "USB_DP_47") (pintype "bidirectional"))
    )
    (net (code "55") (name "Net-(U3-ILIM{slash}VSET)") (class "Default")
      (node (ref "R12") (pin "2") (pinfunction "2_2") (pintype "passive"))
      (node (ref "U3") (pin "7") (pinfunction "ILIM/VSET_7") (pintype "input"))
    )
    (net (code "56") (name "Net-(U3-ISET)") (class "Default")
      (node (ref "R14") (pin "2") (pinfunction "2_2") (pintype "passive"))
      (node (ref "U3") (pin "8") (pinfunction "ISET_8") (pintype "input"))
    )
    (net (code "57") (name "Net-(U3-STAT1)") (class "Default")
      (node (ref "R9") (pin "2") (pinfunction "2_2") (pintype "passive"))
      (node (ref "U3") (pin "9") (pinfunction "STAT1_9") (pintype "output"))
    )
    (net (code "58") (name "Net-(U3-STAT2)") (class "Default")
      (node (ref "R10") (pin "2") (pinfunction "2_2") (pintype "passive"))
      (node (ref "U3") (pin "3") (pinfunction "STAT2_3") (pintype "output"))
    )
    (net (code "59") (name "Net-(U3-TS{slash}MR)") (class "Default")
      (node (ref "R13") (pin "2") (pinfunction "2_2") (pintype "passive"))
      (node (ref "U3") (pin "6") (pinfunction "TS/MR_6") (pintype "input"))
    )
    (net (code "60") (name "Net-(U4-EN)") (class "Default")
      (node (ref "R11") (pin "1") (pinfunction "1_1") (pintype "passive"))
      (node (ref "U4") (pin "2") (pinfunction "EN_2") (pintype "input"))
    )
    (net (code "61") (name "Net-(U4-FB)") (class "Default")
      (node (ref "R15") (pin "1") (pinfunction "1_1") (pintype "passive"))
      (node (ref "R16") (pin "2") (pinfunction "2_2") (pintype "passive"))
      (node (ref "U4") (pin "1") (pinfunction "FB_1") (pintype "input"))
    )
    (net (code "62") (name "Net-(U7-MICBIAS)") (class "Default")
      (node (ref "R22") (pin "1") (pinfunction "1_1") (pintype "passive"))
      (node (ref "U7") (pin "12") (pinfunction "MICBIAS_12") (pintype "output"))
    )
    (net (code "63") (name "Net-(U7-~{RESET})") (class "Default")
      (node (ref "C33") (pin "1") (pinfunction "1_1") (pintype "passive"))
      (node (ref "R21") (pin "1") (pinfunction "1_1") (pintype "passive"))
      (node (ref "U7") (pin "31") (pinfunction "~{RESET}_31") (pintype "input"))
    )
    (net (code "64") (name "OUTL") (class "Default")
      (node (ref "C22") (pin "2") (pinfunction "2_2") (pintype "passive"))
      (node (ref "J2") (pin "4") (pinfunction "4_4") (pintype "passive"))
      (node (ref "J2") (pin "5") (pinfunction "5_5") (pintype "passive"))
    )
    (net (code "65") (name "OUTR") (class "Default")
      (node (ref "C23") (pin "2") (pinfunction "2_2") (pintype "passive"))
      (node (ref "J2") (pin "3") (pinfunction "3_3") (pintype "passive"))
      (node (ref "J2") (pin "6") (pinfunction "6_6") (pintype "passive"))
    )
    (net (code "66") (name "PWR_BTN") (class "Default")
      (node (ref "D4") (pin "1") (pinfunction "C_1") (pintype "passive"))
      (node (ref "D5") (pin "1") (pinfunction "C_1") (pintype "passive"))
      (node (ref "J4") (pin "6") (pinfunction "6_6") (pintype "passive"))
      (node (ref "TP11") (pin "TP") (pinfunction "TP_TP") (pintype "input"))
    )
    (net (code "67") (name "PWR_OFF") (class "Default")
      (node (ref "R25") (pin "1") (pinfunction "1_1") (pintype "passive"))
      (node (ref "TP10") (pin "TP") (pinfunction "TP_TP") (pintype "input"))
      (node (ref "U$1") (pin "P$114") (pinfunction "GPIO2_P$114") (pintype "bidirectional"))
    )
    (net (code "68") (name "QSPI_SCLK") (class "Default")
      (node (ref "U2") (pin "52") (pinfunction "QSPI_SCLK_52") (pintype "bidirectional"))
      (node (ref "U8") (pin "6") (pinfunction "CLK_6") (pintype "input"))
    )
    (net (code "69") (name "QSPI_SD0") (class "Default")
      (node (ref "U2") (pin "53") (pinfunction "QSPI_SD0_53") (pintype "bidirectional"))
      (node (ref "U8") (pin "5") (pinfunction "DI(IO0)_5") (pintype "bidirectional"))
    )
    (net (code "70") (name "QSPI_SD1") (class "Default")
      (node (ref "U2") (pin "55") (pinfunction "QSPI_SD1_55") (pintype "bidirectional"))
      (node (ref "U8") (pin "2") (pinfunction "DO(IO1)_2") (pintype "bidirectional"))
    )
    (net (code "71") (name "QSPI_SD2") (class "Default")
      (node (ref "U2") (pin "54") (pinfunction "QSPI_SD2_54") (pintype "bidirectional"))
      (node (ref "U8") (pin "3") (pinfunction "~{WP}(IO2)_3") (pintype "bidirectional"))
    )
    (net (code "72") (name "QSPI_SD3") (class "Default")
      (node (ref "U2") (pin "51") (pinfunction "QSPI_SD3_51") (pintype "bidirectional"))
      (node (ref "U8") (pin "7") (pinfunction "~{HOLD/RESET}(IO3)_7") (pintype "bidirectional"))
    )
    (net (code "73") (name "QSPI_SS") (class "Default")
      (node (ref "R1") (pin "1") (pinfunction "1_1") (pintype "passive"))
      (node (ref "R3") (pin "2") (pinfunction "2_2") (pintype "passive"))
      (node (ref "U2") (pin "56") (pinfunction "QSPI_SS_N_56") (pintype "bidirectional"))
      (node (ref "U8") (pin "1") (pinfunction "~{CS}_1") (pintype "input"))
    )
    (net (code "74") (name "ROW0") (class "Default")
      (node (ref "SW_E") (pin "3") (pinfunction "3_3") (pintype "passive"))
      (node (ref "SW_E") (pin "4") (pinfunction "4_4") (pintype "passive"))
      (node (ref "SW_I") (pin "3") (pinfunction "3_3") (pintype "passive"))
      (node (ref "SW_I") (pin "4") (pinfunction "4_4") (pintype "passive"))
      (node (ref "SW_O") (pin "3") (pinfunction "3_3") (pintype "passive"))
      (node (ref "SW_O") (pin "4") (pinfunction "4_4") (pintype "passive"))
      (node (ref "SW_P") (pin "3") (pinfunction "3_3") (pintype "passive"))
      (node (ref "SW_P") (pin "4") (pinfunction "4_4") (pintype "passive"))
      (node (ref "SW_Q") (pin "3") (pinfunction "3_3") (pintype "passive"))
      (node (ref "SW_Q") (pin "4") (pinfunction "4_4") (pintype "passive"))
      (node (ref "SW_R") (pin "3") (pinfunction "3_3") (pintype "passive"))
      (node (ref "SW_R") (pin "4") (pinfunction "4_4") (pintype "passive"))
      (node (ref "SW_T") (pin "3") (pinfunction "3_3") (pintype "passive"))
      (node (ref "SW_T") (pin "4") (pinfunction "4_4") (pintype "passive"))
      (node (ref "SW_U") (pin "3") (pinfunction "3_3") (pintype "passive"))
      (node (ref "SW_U") (pin "4") (pinfunction "4_4") (pintype "passive"))
      (node (ref "SW_W") (pin "3") (pinfunction "3_3") (pintype "passive"))
      (node (ref "SW_W") (pin "4") (pinfunction "4_4") (pintype "passive"))
      (node (ref "SW_Y") (pin "3") (pinfunction "3_3") (pintype "passive"))
      (node (ref "SW_Y") (pin "4") (pinfunction "4_4") (pintype "passive"))
      (node (ref "U2") (pin "14") (pinfunction "GPIO11_14") (pintype "bidirectional"))
    )
    (net (code "75") (name "ROW1") (class "Default")
      (node (ref "SW_A") (pin "3") (pinfunction "3_3") (pintype "passive"))
      (node (ref "SW_A") (pin "4") (pinfunction "4_4") (pintype "passive"))
      (node (ref "SW_BSP") (pin "3") (pinfunction "3_3") (pintype "passive"))
      (node (ref "SW_BSP") (pin "4") (pinfunction "4_4") (pintype "passive"))
      (node (ref "SW_D") (pin "3") (pinfunction "3_3") (pintype "passive"))
      (node (ref "SW_D") (pin "4") (pinfunction "4_4") (pintype "passive"))
      (node (ref "SW_F") (pin "3") (pinfunction "3_3") (pintype "passive"))
      (node (ref "SW_F") (pin "4") (pinfunction "4_4") (pintype "passive"))
      (node (ref "SW_G") (pin "3") (pinfunction "3_3") (pintype "passive"))
      (node (ref "SW_G") (pin "4") (pinfunction "4_4") (pintype "passive"))
      (node (ref "SW_H") (pin "3") (pinfunction "3_3") (pintype "passive"))
      (node (ref "SW_H") (pin "4") (pinfunction "4_4") (pintype "passive"))
      (node (ref "SW_J") (pin "3") (pinfunction "3_3") (pintype "passive"))
      (node (ref "SW_J") (pin "4") (pinfunction "4_4") (pintype "passive"))
      (node (ref "SW_K") (pin "3") (pinfunction "3_3") (pintype "passive"))
      (node (ref "SW_K") (pin "4") (pinfunction "4_4") (pintype "passive"))
      (node (ref "SW_L") (pin "3") (pinfunction "3_3") (pintype "passive"))
      (node (ref "SW_L") (pin "4") (pinfunction "4_4") (pintype "passive"))
      (node (ref "SW_S") (pin "3") (pinfunction "3_3") (pintype "passive"))
      (node (ref "SW_S") (pin "4") (pinfunction "4_4") (pintype "passive"))
      (node (ref "U2") (pin "15") (pinfunction "GPIO12_15") (pintype "bidirectional"))
    )
    (net (code "76") (name "ROW2") (class "Default")
      (node (ref "SW_.") (pin "3") (pinfunction "3_3") (pintype "passive"))
      (node (ref "SW_.") (pin "4") (pinfunction "4_4") (pintype "passive"))
      (node (ref "SW_?") (pin "3") (pinfunction "3_3") (pintype "passive"))
      (node (ref "SW_?") (pin "4") (pinfunction "4_4") (pintype "passive"))
      (node (ref "SW_B") (pin "3") (pinfunction "3_3") (pintype "passive"))
      (node (ref "SW_B") (pin "4") (pinfunction "4_4") (pintype "passive"))
      (node (ref "SW_C") (pin "3") (pinfunction "3_3") (pintype "passive"))
      (node (ref "SW_C") (pin "4") (pinfunction "4_4") (pintype "passive"))
      (node (ref "SW_ENTER") (pin "3") (pinfunction "3_3") (pintype "passive"))
      (node (ref "SW_ENTER") (pin "4") (pinfunction "4_4") (pintype "passive"))
      (node (ref "SW_M") (pin "3") (pinfunction "3_3") (pintype "passive"))
      (node (ref "SW_M") (pin "4") (pinfunction "4_4") (pintype "passive"))
      (node (ref "SW_N") (pin "3") (pinfunction "3_3") (pintype "passive"))
      (node (ref "SW_N") (pin "4") (pinfunction "4_4") (pintype "passive"))
      (node (ref "SW_V") (pin "3") (pinfunction "3_3") (pintype "passive"))
      (node (ref "SW_V") (pin "4") (pinfunction "4_4") (pintype "passive"))
      (node (ref "SW_X") (pin "3") (pinfunction "3_3") (pintype "passive"))
      (node (ref "SW_X") (pin "4") (pinfunction "4_4") (pintype "passive"))
      (node (ref "SW_Z") (pin "3") (pinfunction "3_3") (pintype "passive"))
      (node (ref "SW_Z") (pin "4") (pinfunction "4_4") (pintype "passive"))
      (node (ref "U2") (pin "16") (pinfunction "GPIO13_16") (pintype "bidirectional"))
    )
    (net (code "77") (name "ROW3") (class "Default")
      (node (ref "SW_/") (pin "3") (pinfunction "3_3") (pintype "passive"))
      (node (ref "SW_/") (pin "4") (pinfunction "4_4") (pintype "passive"))
      (node (ref "SW_ALT") (pin "3") (pinfunction "3_3") (pintype "passive"))
      (node (ref "SW_ALT") (pin "4") (pinfunction "4_4") (pintype "passive"))
      (node (ref "SW_CMD") (pin "3") (pinfunction "3_3") (pintype "passive"))
      (node (ref "SW_CMD") (pin "4") (pinfunction "4_4") (pintype "passive"))
      (node (ref "SW_CTL") (pin "3") (pinfunction "3_3") (pintype "passive"))
      (node (ref "SW_CTL") (pin "4") (pinfunction "4_4") (pintype "passive"))
      (node (ref "SW_SHFT") (pin "3") (pinfunction "3_3") (pintype "passive"))
      (node (ref "SW_SHFT") (pin "4") (pinfunction "4_4") (pintype "passive"))
      (node (ref "SW_SP1") (pin "3") (pinfunction "3_3") (pintype "passive"))
      (node (ref "SW_SP1") (pin "4") (pinfunction "4_4") (pintype "passive"))
      (node (ref "SW_SP2") (pin "3") (pinfunction "3_3") (pintype "passive"))
      (node (ref "SW_SP2") (pin "4") (pinfunction "4_4") (pintype "passive"))
      (node (ref "SW_SYM") (pin "3") (pinfunction "3_3") (pintype "passive"))
      (node (ref "SW_SYM") (pin "4") (pinfunction "4_4") (pintype "passive"))
      (node (ref "SW_TAB") (pin "3") (pinfunction "3_3") (pintype "passive"))
      (node (ref "SW_TAB") (pin "4") (pinfunction "4_4") (pintype "passive"))
      (node (ref "SW_}") (pin "3") (pinfunction "3_3") (pintype "passive"))
      (node (ref "SW_}") (pin "4") (pinfunction "4_4") (pintype "passive"))
      (node (ref "U2") (pin "17") (pinfunction "GPIO14_17") (pintype "bidirectional"))
    )
    (net (code "78") (name "RP2040_USB_N") (class "Default")
      (node (ref "R4") (pin "2") (pinfunction "2_2") (pintype "passive"))
      (node (ref "U5") (pin "4") (pinfunction "D-_4") (pintype "bidirectional"))
    )
    (net (code "79") (name "RP2040_USB_P") (class "Default")
      (node (ref "R5") (pin "1") (pinfunction "1_1") (pintype "passive"))
      (node (ref "U5") (pin "3") (pinfunction "D+_3") (pintype "bidirectional"))
    )
    (net (code "80") (name "SCL") (class "Default")
      (node (ref "R8") (pin "1") (pinfunction "1_1") (pintype "passive"))
      (node (ref "TP5") (pin "TP") (pinfunction "TP_TP") (pintype "input"))
      (node (ref "U$1") (pin "P$43") (pinfunction "SCL0_P$43") (pintype "bidirectional"))
      (node (ref "U2") (pin "39") (pinfunction "GPIO27/ADC1_39") (pintype "bidirectional"))
      (node (ref "U6") (pin "7") (pinfunction "SCL_7") (pintype "input"))
      (node (ref "U7") (pin "10") (pinfunction "SCL_10") (pintype "input"))
    )
    (net (code "81") (name "SDA") (class "Default")
      (node (ref "R7") (pin "1") (pinfunction "1_1") (pintype "passive"))
      (node (ref "TP6") (pin "TP") (pinfunction "TP_TP") (pintype "input"))
      (node (ref "U$1") (pin "P$42") (pinfunction "SDA0_P$42") (pintype "bidirectional"))
      (node (ref "U2") (pin "38") (pinfunction "GPIO26/ADC0_38") (pintype "bidirectional"))
      (node (ref "U6") (pin "8") (pinfunction "SDA_8") (pintype "bidirectional"))
      (node (ref "U7") (pin "9") (pinfunction "SDA_9") (pintype "bidirectional"))
    )
    (net (code "82") (name "SD_CLK") (class "Default")
      (node (ref "J3") (pin "5") (pinfunction "CLK_5") (pintype "input"))
      (node (ref "U$1") (pin "P$127") (pinfunction "SD_CLK_P$127") (pintype "bidirectional"))
    )
    (net (code "83") (name "SD_CMD") (class "Default")
      (node (ref "J3") (pin "3") (pinfunction "CMD_3") (pintype "bidirectional"))
      (node (ref "U$1") (pin "P$128") (pinfunction "SD_CMD_P$128") (pintype "bidirectional"))
    )
    (net (code "84") (name "SD_DAT0") (class "Default")
      (node (ref "J3") (pin "7") (pinfunction "DAT0_7") (pintype "bidirectional"))
      (node (ref "U$1") (pin "P$125") (pinfunction "SD_DAT0_P$125") (pintype "bidirectional"))
    )
    (net (code "85") (name "SD_DAT1") (class "Default")
      (node (ref "J3") (pin "8") (pinfunction "DAT1_8") (pintype "bidirectional"))
      (node (ref "U$1") (pin "P$124") (pinfunction "SD_DAT1_P$124") (pintype "bidirectional"))
    )
    (net (code "86") (name "SD_DAT2") (class "Default")
      (node (ref "J3") (pin "1") (pinfunction "DAT2_1") (pintype "bidirectional"))
      (node (ref "U$1") (pin "P$131") (pinfunction "SD_DAT2_P$131") (pintype "bidirectional"))
    )
    (net (code "87") (name "SD_DAT3") (class "Default")
      (node (ref "J3") (pin "2") (pinfunction "CD/DAT3_2") (pintype "bidirectional"))
      (node (ref "U$1") (pin "P$130") (pinfunction "SD_DAT3_P$130") (pintype "bidirectional"))
    )
    (net (code "88") (name "SELECT") (class "Default")
      (node (ref "SELECT") (pin "1") (pinfunction "1_1") (pintype "passive"))
      (node (ref "SELECT") (pin "2") (pinfunction "2_2") (pintype "passive"))
      (node (ref "U2") (pin "12") (pinfunction "GPIO9_12") (pintype "bidirectional"))
    )
    (net (code "89") (name "SHT_DWN") (class "Default")
      (node (ref "R26") (pin "1") (pinfunction "1_1") (pintype "passive"))
      (node (ref "TP9") (pin "TP") (pinfunction "TP_TP") (pintype "input"))
      (node (ref "U$1") (pin "P$113") (pinfunction "GPIO3_P$113") (pintype "bidirectional"))
    )
    (net (code "90") (name "SPI_CLK") (class "Default")
      (node (ref "J4") (pin "12") (pinfunction "12_12") (pintype "passive"))
      (node (ref "U$1") (pin "P$92") (pinfunction "GPIO11_P$92") (pintype "bidirectional"))
    )
    (net (code "91") (name "SPI_MISO") (class "Default")
      (node (ref "J4") (pin "14") (pinfunction "14_14") (pintype "passive"))
      (node (ref "U$1") (pin "P$95") (pinfunction "GPIO9_P$95") (pintype "bidirectional"))
    )
    (net (code "92") (name "SPI_MOSI") (class "Default")
      (node (ref "J4") (pin "13") (pinfunction "13_13") (pintype "passive"))
      (node (ref "U$1") (pin "P$97") (pinfunction "GPIO10_P$97") (pintype "bidirectional"))
    )
    (net (code "93") (name "SPKM") (class "Default")
      (node (ref "SPEAKER") (pin "M") (pinfunction "M_M") (pintype "passive"))
      (node (ref "U7") (pin "19") (pinfunction "SPKM_19") (pintype "output"))
      (node (ref "U7") (pin "23") (pinfunction "SPKM_23") (pintype "output"))
    )
    (net (code "94") (name "SPKP") (class "Default")
      (node (ref "SPEAKER") (pin "P") (pinfunction "P_P") (pintype "passive"))
      (node (ref "U7") (pin "22") (pinfunction "SPKP_22") (pintype "output"))
      (node (ref "U7") (pin "26") (pinfunction "SPKP_26") (pintype "output"))
    )
    (net (code "95") (name "START") (class "Default")
      (node (ref "START") (pin "1") (pinfunction "1_1") (pintype "passive"))
      (node (ref "START") (pin "2") (pinfunction "2_2") (pintype "passive"))
      (node (ref "U2") (pin "11") (pinfunction "GPIO8_11") (pintype "bidirectional"))
    )
    (net (code "96") (name "SWCLK") (class "Default")
      (node (ref "U2") (pin "24") (pinfunction "SWCLK_24") (pintype "input"))
    )
    (net (code "97") (name "SWDIO") (class "Default")
      (node (ref "U2") (pin "25") (pinfunction "SWDIO_25") (pintype "bidirectional"))
    )
    (net (code "98") (name "USB_N") (class "Default")
      (node (ref "J5") (pin "A7") (pinfunction "DN1_A7") (pintype "passive"))
      (node (ref "J5") (pin "B7") (pinfunction "DN2_B7") (pintype "passive"))
      (node (ref "U5") (pin "8") (pinfunction "HSD2-_8") (pintype "bidirectional"))
    )
    (net (code "99") (name "USB_P") (class "Default")
      (node (ref "J5") (pin "A6") (pinfunction "DP1_A6") (pintype "passive"))
      (node (ref "J5") (pin "B6") (pinfunction "DP2_B6") (pintype "passive"))
      (node (ref "U5") (pin "9") (pinfunction "HSD2+_9") (pintype "bidirectional"))
    )
    (net (code "100") (name "USB_SELECT") (class "Default")
      (node (ref "JP2") (pin "1") (pinfunction "1_1") (pintype "passive"))
      (node (ref "R27") (pin "1") (pinfunction "1_1") (pintype "passive"))
      (node (ref "U5") (pin "2") (pinfunction "SEL_2") (pintype "input"))
    )
    (net (code "101") (name "VBAT") (class "Default")
      (node (ref "BAT") (pin "1") (pinfunction "1_1") (pintype "passive"))
      (node (ref "C20") (pin "1") (pinfunction "1_1") (pintype "passive"))
      (node (ref "C21") (pin "1") (pinfunction "1_1") (pintype "passive"))
      (node (ref "U3") (pin "2") (pinfunction "BAT_2") (pintype "output"))
      (node (ref "U6") (pin "2") (pinfunction "CELL_2") (pintype "power_in"))
      (node (ref "U6") (pin "3") (pinfunction "VDD_3") (pintype "power_in"))
    )
    (net (code "102") (name "VBUS") (class "Default")
      (node (ref "C15") (pin "1") (pinfunction "1_1") (pintype "passive"))
      (node (ref "J5") (pin "A4_B9") (pinfunction "VBUS_A4_B9") (pintype "passive"))
      (node (ref "J5") (pin "B4_A9") (pinfunction "VBUS_B4_A9") (pintype "passive"))
      (node (ref "R28") (pin "1") (pinfunction "1_1") (pintype "passive"))
      (node (ref "U3") (pin "10") (pinfunction "IN_10") (pintype "input"))
    )
    (net (code "103") (name "VSYS") (class "Default")
      (node (ref "C16") (pin "1") (pinfunction "1_1") (pintype "passive"))
      (node (ref "C24") (pin "1") (pinfunction "1_1") (pintype "passive"))
      (node (ref "D1") (pin "A") (pinfunction "A_A") (pintype "passive"))
      (node (ref "D2") (pin "A") (pinfunction "A_A") (pintype "passive"))
      (node (ref "Q1") (pin "2") (pinfunction "S_2") (pintype "passive"))
      (node (ref "R23") (pin "2") (pinfunction "2_2") (pintype "passive"))
      (node (ref "TP8") (pin "TP") (pinfunction "TP_TP") (pintype "input"))
      (node (ref "U3") (pin "1") (pinfunction "SYS_1") (pintype "output"))
    )
    (net (code "104") (name "VSYS_ON") (class "Default")
      (node (ref "C17") (pin "1") (pinfunction "1_1") (pintype "passive"))
      (node (ref "L1") (pin "1") (pinfunction "1_1") (pintype "passive"))
      (node (ref "Q1") (pin "3") (pinfunction "D_3") (pintype "passive"))
      (node (ref "R11") (pin "2") (pinfunction "2_2") (pintype "passive"))
      (node (ref "TP7") (pin "TP") (pinfunction "TP_TP") (pintype "input"))
      (node (ref "U4") (pin "3") (pinfunction "VIN_3") (pintype "power_in"))
    )
    (net (code "105") (name "XIN") (class "Default")
      (node (ref "C2") (pin "2") (pinfunction "2_2") (pintype "passive"))
      (node (ref "U2") (pin "20") (pinfunction "XIN_20") (pintype "input"))
      (node (ref "Y1") (pin "1") (pinfunction "1_1") (pintype "passive"))
    )
    (net (code "106") (name "XOUT") (class "Default")
      (node (ref "R2") (pin "2") (pinfunction "2_2") (pintype "passive"))
      (node (ref "U2") (pin "21") (pinfunction "XOUT_21") (pintype "output"))
    )
    (net (code "107") (name "unconnected-(J3-PadCD)") (class "Default")
      (node (ref "J3") (pin "CD") (pinfunction "CD_CD") (pintype "passive"))
    )
    (net (code "108") (name "unconnected-(J5-SBU1-PadA8)") (class "Default")
      (node (ref "J5") (pin "A8") (pinfunction "SBU1_A8") (pintype "passive"))
    )
    (net (code "109") (name "unconnected-(J5-SBU2-PadB8)") (class "Default")
      (node (ref "J5") (pin "B8") (pinfunction "SBU2_B8") (pintype "passive"))
    )
    (net (code "110") (name "unconnected-(U$1-BT_ON-PadP$117)") (class "Default")
      (node (ref "U$1") (pin "P$117") (pinfunction "BT_ON_P$117") (pintype "bidirectional"))
    )
    (net (code "111") (name "unconnected-(U$1-CAM_GPIO-PadP$44)") (class "Default")
      (node (ref "U$1") (pin "P$44") (pinfunction "CAM_GPIO_P$44") (pintype "bidirectional"))
    )
    (net (code "112") (name "unconnected-(U$1-CSI_CK_N-PadP$53)") (class "Default")
      (node (ref "U$1") (pin "P$53") (pinfunction "CSI_CK_N_P$53") (pintype "bidirectional"))
    )
    (net (code "113") (name "unconnected-(U$1-CSI_CK_P-PadP$52)") (class "Default")
      (node (ref "U$1") (pin "P$52") (pinfunction "CSI_CK_P_P$52") (pintype "bidirectional"))
    )
    (net (code "114") (name "unconnected-(U$1-CSI_D0_N-PadP$59)") (class "Default")
      (node (ref "U$1") (pin "P$59") (pinfunction "CSI_D0_N_P$59") (pintype "bidirectional"))
    )
    (net (code "115") (name "unconnected-(U$1-CSI_D0_P-PadP$58)") (class "Default")
      (node (ref "U$1") (pin "P$58") (pinfunction "CSI_D0_P_P$58") (pintype "bidirectional"))
    )
    (net (code "116") (name "unconnected-(U$1-CSI_D1_N-PadP$56)") (class "Default")
      (node (ref "U$1") (pin "P$56") (pinfunction "CSI_D1_N_P$56") (pintype "bidirectional"))
    )
    (net (code "117") (name "unconnected-(U$1-CSI_D1_P-PadP$55)") (class "Default")
      (node (ref "U$1") (pin "P$55") (pinfunction "CSI_D1_P_P$55") (pintype "bidirectional"))
    )
    (net (code "118") (name "unconnected-(U$1-CSI_D2_N-PadP$50)") (class "Default")
      (node (ref "U$1") (pin "P$50") (pinfunction "CSI_D2_N_P$50") (pintype "bidirectional"))
    )
    (net (code "119") (name "unconnected-(U$1-CSI_D2_P-PadP$49)") (class "Default")
      (node (ref "U$1") (pin "P$49") (pinfunction "CSI_D2_P_P$49") (pintype "bidirectional"))
    )
    (net (code "120") (name "unconnected-(U$1-CSI_D3_N-PadP$47)") (class "Default")
      (node (ref "U$1") (pin "P$47") (pinfunction "CSI_D3_N_P$47") (pintype "bidirectional"))
    )
    (net (code "121") (name "unconnected-(U$1-CSI_D3_P-PadP$46)") (class "Default")
      (node (ref "U$1") (pin "P$46") (pinfunction "CSI_D3_P_P$46") (pintype "bidirectional"))
    )
    (net (code "122") (name "unconnected-(U$1-CVBS-PadP$39)") (class "Default")
      (node (ref "U$1") (pin "P$39") (pinfunction "CVBS_P$39") (pintype "bidirectional"))
    )
    (net (code "123") (name "unconnected-(U$1-DSI_CK_N-PadP$9)") (class "Default")
      (node (ref "U$1") (pin "P$9") (pinfunction "DSI_CK_N_P$9") (pintype "bidirectional"))
    )
    (net (code "124") (name "unconnected-(U$1-DSI_CL_P-PadP$8)") (class "Default")
      (node (ref "U$1") (pin "P$8") (pinfunction "DSI_CL_P_P$8") (pintype "bidirectional"))
    )
    (net (code "125") (name "unconnected-(U$1-DSI_D0_N-PadP$15)") (class "Default")
      (node (ref "U$1") (pin "P$15") (pinfunction "DSI_D0_N_P$15") (pintype "bidirectional"))
    )
    (net (code "126") (name "unconnected-(U$1-DSI_D0_P-PadP$14)") (class "Default")
      (node (ref "U$1") (pin "P$14") (pinfunction "DSI_D0_P_P$14") (pintype "bidirectional"))
    )
    (net (code "127") (name "unconnected-(U$1-DSI_D1_N-PadP$12)") (class "Default")
      (node (ref "U$1") (pin "P$12") (pinfunction "DSI_D1_N_P$12") (pintype "bidirectional"))
    )
    (net (code "128") (name "unconnected-(U$1-DSI_D1_P-PadP$11)") (class "Default")
      (node (ref "U$1") (pin "P$11") (pinfunction "DSI_D1_P_P$11") (pintype "bidirectional"))
    )
    (net (code "129") (name "unconnected-(U$1-DSI_D2_N-PadP$6)") (class "Default")
      (node (ref "U$1") (pin "P$6") (pinfunction "DSI_D2_N_P$6") (pintype "bidirectional"))
    )
    (net (code "130") (name "unconnected-(U$1-DSI_D2_P-PadP$5)") (class "Default")
      (node (ref "U$1") (pin "P$5") (pinfunction "DSI_D2_P_P$5") (pintype "bidirectional"))
    )
    (net (code "131") (name "unconnected-(U$1-DSI_D3_N-PadP$3)") (class "Default")
      (node (ref "U$1") (pin "P$3") (pinfunction "DSI_D3_N_P$3") (pintype "bidirectional"))
    )
    (net (code "132") (name "unconnected-(U$1-DSI_D3_P-PadP$2)") (class "Default")
      (node (ref "U$1") (pin "P$2") (pinfunction "DSI_D3_P_P$2") (pintype "bidirectional"))
    )
    (net (code "133") (name "unconnected-(U$1-GLOBAL_EN-PadP$62)") (class "Default")
      (node (ref "U$1") (pin "P$62") (pinfunction "GLOBAL_EN_P$62") (pintype "bidirectional"))
    )
    (net (code "134") (name "unconnected-(U$1-GPIO4-PadP$111)") (class "Default")
      (node (ref "U$1") (pin "P$111") (pinfunction "GPIO4_P$111") (pintype "bidirectional"))
    )
    (net (code "135") (name "unconnected-(U$1-GPIO5-PadP$85)") (class "Default")
      (node (ref "U$1") (pin "P$85") (pinfunction "GPIO5_P$85") (pintype "bidirectional"))
    )
    (net (code "136") (name "unconnected-(U$1-GPIO6-PadP$83)") (class "Default")
      (node (ref "U$1") (pin "P$83") (pinfunction "GPIO6_P$83") (pintype "bidirectional"))
    )
    (net (code "137") (name "unconnected-(U$1-GPIO13-PadP$80)") (class "Default")
      (node (ref "U$1") (pin "P$80") (pinfunction "GPIO13_P$80") (pintype "bidirectional"))
    )
    (net (code "138") (name "unconnected-(U$1-GPIO14-PadP$110)") (class "Default")
      (node (ref "U$1") (pin "P$110") (pinfunction "GPIO14_P$110") (pintype "bidirectional"))
    )
    (net (code "139") (name "unconnected-(U$1-GPIO15-PadP$108)") (class "Default")
      (node (ref "U$1") (pin "P$108") (pinfunction "GPIO15_P$108") (pintype "bidirectional"))
    )
    (net (code "140") (name "unconnected-(U$1-GPIO16-PadP$77)") (class "Default")
      (node (ref "U$1") (pin "P$77") (pinfunction "GPIO16_P$77") (pintype "bidirectional"))
    )
    (net (code "141") (name "unconnected-(U$1-GPIO17-PadP$107)") (class "Default")
      (node (ref "U$1") (pin "P$107") (pinfunction "GPIO17_P$107") (pintype "bidirectional"))
    )
    (net (code "142") (name "unconnected-(U$1-GPIO22-PadP$102)") (class "Default")
      (node (ref "U$1") (pin "P$102") (pinfunction "GPIO22_P$102") (pintype "bidirectional"))
    )
    (net (code "143") (name "unconnected-(U$1-GPIO23-PadP$101)") (class "Default")
      (node (ref "U$1") (pin "P$101") (pinfunction "GPIO23_P$101") (pintype "bidirectional"))
    )
    (net (code "144") (name "unconnected-(U$1-GPIO26-PadP$76)") (class "Default")
      (node (ref "U$1") (pin "P$76") (pinfunction "GPIO26_P$76") (pintype "bidirectional"))
    )
    (net (code "145") (name "unconnected-(U$1-GPIO27-PadP$104)") (class "Default")
      (node (ref "U$1") (pin "P$104") (pinfunction "GPIO27_P$104") (pintype "bidirectional"))
    )
    (net (code "146") (name "unconnected-(U$1-HDMI_CEC-PadP$20)") (class "Default")
      (node (ref "U$1") (pin "P$20") (pinfunction "HDMI_CEC_P$20") (pintype "bidirectional"))
    )
    (net (code "147") (name "unconnected-(U$1-HDMI_CK_N-PadP$22)") (class "Default")
      (node (ref "U$1") (pin "P$22") (pinfunction "HDMI_CK_N_P$22") (pintype "bidirectional"))
    )
    (net (code "148") (name "unconnected-(U$1-HDMI_CK_P-PadP$23)") (class "Default")
      (node (ref "U$1") (pin "P$23") (pinfunction "HDMI_CK_P_P$23") (pintype "bidirectional"))
    )
    (net (code "149") (name "unconnected-(U$1-HDMI_D0_N-PadP$25)") (class "Default")
      (node (ref "U$1") (pin "P$25") (pinfunction "HDMI_D0_N_P$25") (pintype "bidirectional"))
    )
    (net (code "150") (name "unconnected-(U$1-HDMI_D0_P-PadP$26)") (class "Default")
      (node (ref "U$1") (pin "P$26") (pinfunction "HDMI_D0_P_P$26") (pintype "bidirectional"))
    )
    (net (code "151") (name "unconnected-(U$1-HDMI_D1_N-PadP$28)") (class "Default")
      (node (ref "U$1") (pin "P$28") (pinfunction "HDMI_D1_N_P$28") (pintype "bidirectional"))
    )
    (net (code "152") (name "unconnected-(U$1-HDMI_D1_P-PadP$29)") (class "Default")
      (node (ref "U$1") (pin "P$29") (pinfunction "HDMI_D1_P_P$29") (pintype "bidirectional"))
    )
    (net (code "153") (name "unconnected-(U$1-HDMI_D2_N-PadP$31)") (class "Default")
      (node (ref "U$1") (pin "P$31") (pinfunction "HDMI_D2_N_P$31") (pintype "bidirectional"))
    )
    (net (code "154") (name "unconnected-(U$1-HDMI_D2_P-PadP$32)") (class "Default")
      (node (ref "U$1") (pin "P$32") (pinfunction "HDMI_D2_P_P$32") (pintype "bidirectional"))
    )
    (net (code "155") (name "unconnected-(U$1-HDMI_HPD-PadP$17)") (class "Default")
      (node (ref "U$1") (pin "P$17") (pinfunction "HDMI_HPD_P$17") (pintype "bidirectional"))
    )
    (net (code "156") (name "unconnected-(U$1-HDMI_SCL-PadP$19)") (class "Default")
      (node (ref "U$1") (pin "P$19") (pinfunction "HDMI_SCL_P$19") (pintype "bidirectional"))
    )
    (net (code "157") (name "unconnected-(U$1-HDMI_SDA-PadP$18)") (class "Default")
      (node (ref "U$1") (pin "P$18") (pinfunction "HDMI_SDA_P$18") (pintype "bidirectional"))
    )
    (net (code "158") (name "unconnected-(U$1-ID_SC-PadP$86)") (class "Default")
      (node (ref "U$1") (pin "P$86") (pinfunction "ID_SC_P$86") (pintype "bidirectional"))
    )
    (net (code "159") (name "unconnected-(U$1-ID_SD-PadP$88)") (class "Default")
      (node (ref "U$1") (pin "P$88") (pinfunction "ID_SD_P$88") (pintype "bidirectional"))
    )
    (net (code "160") (name "unconnected-(U$1-NC1-PadP$70)") (class "Default")
      (node (ref "U$1") (pin "P$70") (pinfunction "NC1_P$70") (pintype "no_connect"))
    )
    (net (code "161") (name "unconnected-(U$1-NC2-PadP$71)") (class "Default")
      (node (ref "U$1") (pin "P$71") (pinfunction "NC2_P$71") (pintype "no_connect"))
    )
    (net (code "162") (name "unconnected-(U$1-RPI_BOOT-PadP$121)") (class "Default")
      (node (ref "U$1") (pin "P$121") (pinfunction "RPI_BOOT_P$121") (pintype "bidirectional"))
    )
    (net (code "163") (name "unconnected-(U$1-RUN_PG-PadP$61)") (class "Default")
      (node (ref "U$1") (pin "P$61") (pinfunction "RUN_PG_P$61") (pintype "bidirectional"))
    )
    (net (code "164") (name "unconnected-(U$1-USB_OTG-PadP$38)") (class "Default")
      (node (ref "U$1") (pin "P$38") (pinfunction "USB_OTG_P$38") (pintype "bidirectional"))
    )
    (net (code "165") (name "unconnected-(U$1-WIFI_ON-PadP$116)") (class "Default")
      (node (ref "U$1") (pin "P$116") (pinfunction "WIFI_ON_P$116") (pintype "bidirectional"))
    )
    (net (code "166") (name "unconnected-(U2-GPIO10-Pad13)") (class "Default")
      (node (ref "U2") (pin "13") (pinfunction "GPIO10_13") (pintype "bidirectional"))
    )
    (net (code "167") (name "unconnected-(U2-GPIO25-Pad37)") (class "Default")
      (node (ref "U2") (pin "37") (pinfunction "GPIO25_37") (pintype "bidirectional"))
    )
    (net (code "168") (name "unconnected-(U2-GPIO28{slash}ADC2-Pad40)") (class "Default")
      (node (ref "U2") (pin "40") (pinfunction "GPIO28/ADC2_40") (pintype "bidirectional"))
    )
    (net (code "169") (name "unconnected-(U2-GPIO29{slash}ADC3-Pad41)") (class "Default")
      (node (ref "U2") (pin "41") (pinfunction "GPIO29/ADC3_41") (pintype "bidirectional"))
    )
    (net (code "170") (name "unconnected-(U7-AIN1-Pad13)") (class "Default")
      (node (ref "U7") (pin "13") (pinfunction "AIN1_13") (pintype "input"))
    )
    (net (code "171") (name "unconnected-(U7-AIN2-Pad14)") (class "Default")
      (node (ref "U7") (pin "14") (pinfunction "AIN2_14") (pintype "input"))
    )
    (net (code "172") (name "unconnected-(U7-MCLK-Pad8)") (class "Default")
      (node (ref "U7") (pin "8") (pinfunction "MCLK_8") (pintype "input"))
    )
  )
)
